# S10B-M-V2_0.net
KiCad netlist of a schematic drawn in Altium Designer
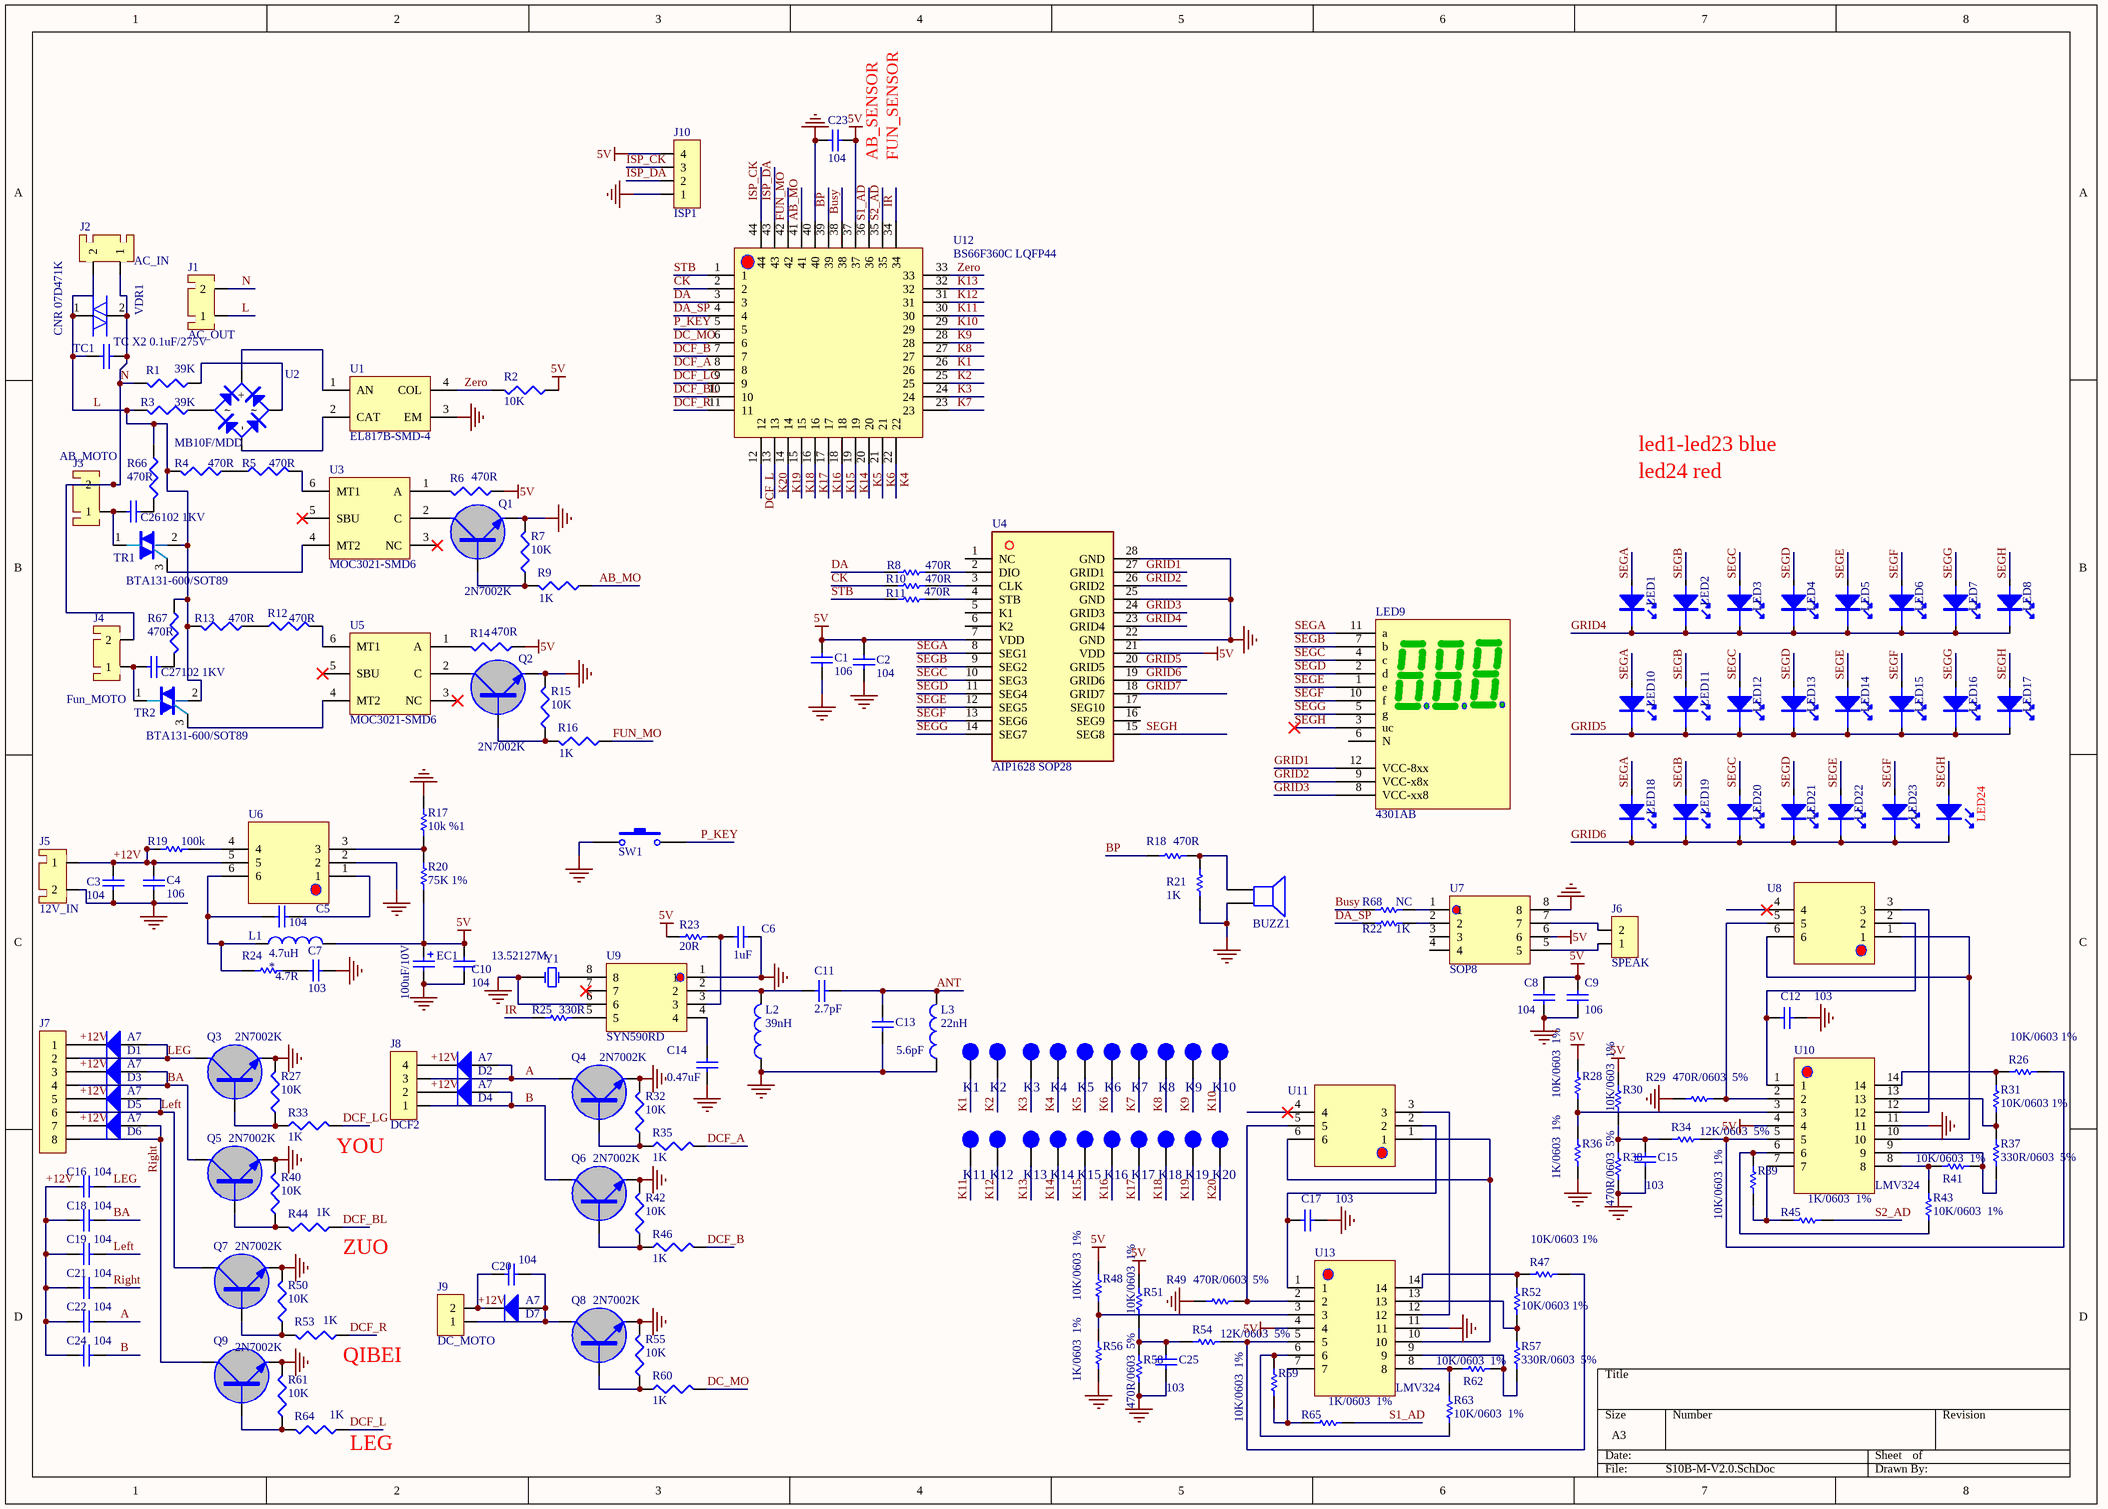
[diagram p0: S10B-M-V2.0.SchDoc]

(export (version "E")
  (design (tool "Eeschema 10.0.6"))
  (components
    (comp (ref "BUZZ1")
      (value "Speaker")
      (footprint "BUZ-1407-7.5")
      (description "Loudspeaker")
      (fields (field (name "MANUFACTURER") "Generic Components"))
      (libsource (lib "Miscellaneous Devices") (part "Speaker"))
    )
    (comp (ref "C1")
      (value "106")
      (footprint "0805C")
      (description "Capacitor")
      (fields
        (field (name "MANUFACTURER") "Generic Components")
        (field (name "PUBLISHER") "Altium Hobart Technology Centre")
      )
      (libsource (lib "Miscellaneous Devices") (part "Cap"))
    )
    (comp (ref "C2")
      (value "104")
      (footprint "0603C")
      (description "Capacitor")
      (fields
        (field (name "MANUFACTURER") "Generic Components")
        (field (name "PUBLISHER") "Altium Hobart Technology Centre")
      )
      (libsource (lib "Miscellaneous Devices") (part "Cap"))
    )
    (comp (ref "C3")
      (value "104")
      (footprint "0603C")
      (description "Capacitor")
      (fields (field (name "PUBLISHER") "Altium Limited"))
      (libsource (lib "Phil") (part "Cap"))
    )
    (comp (ref "C4")
      (value "106")
      (footprint "0805C")
      (description "Capacitor")
      (fields
        (field (name "MANUFACTURER") "Generic Components")
        (field (name "PUBLISHER") "Altium Hobart Technology Centre")
      )
      (libsource (lib "Miscellaneous Devices") (part "Cap"))
    )
    (comp (ref "C5")
      (value "104")
      (footprint "0603C")
      (description "Capacitor")
      (fields
        (field (name "MANUFACTURER") "Generic Components")
        (field (name "PUBLISHER") "Altium Hobart Technology Centre")
      )
      (libsource (lib "Miscellaneous Devices") (part "Cap"))
    )
    (comp (ref "C6")
      (value "1uF")
      (footprint "0603C")
      (description "Capacitor")
      (fields (field (name "PUBLISHER") "Altium Limited"))
      (libsource (lib "Phil") (part "Cap"))
    )
    (comp (ref "C7")
      (value "103")
      (footprint "0603C")
      (description "Capacitor")
      (fields (field (name "PUBLISHER") "Altium Limited"))
      (libsource (lib "Phil") (part "Cap"))
    )
    (comp (ref "C8")
      (value "104")
      (footprint "0603C")
      (description "Capacitor")
      (fields
        (field (name "MANUFACTURER") "Generic Components")
        (field (name "PUBLISHER") "Altium Hobart Technology Centre")
      )
      (libsource (lib "Miscellaneous Devices") (part "Cap"))
    )
    (comp (ref "C9")
      (value "106")
      (footprint "0805C")
      (description "Capacitor")
      (fields
        (field (name "MANUFACTURER") "Generic Components")
        (field (name "PUBLISHER") "Altium Hobart Technology Centre")
      )
      (libsource (lib "Miscellaneous Devices") (part "Cap"))
    )
    (comp (ref "C10")
      (value "104")
      (footprint "0603C")
      (description "Capacitor")
      (fields
        (field (name "MANUFACTURER") "Generic Components")
        (field (name "PUBLISHER") "Altium Hobart Technology Centre")
      )
      (libsource (lib "Miscellaneous Devices") (part "Cap"))
    )
    (comp (ref "C11")
      (value "2.7pF")
      (footprint "0603C")
      (description "Capacitor")
      (fields (field (name "PUBLISHER") "Altium Limited"))
      (libsource (lib "Phil") (part "Cap"))
    )
    (comp (ref "C12")
      (value "103")
      (footprint "0603C")
      (description "Capacitor")
      (fields (field (name "PUBLISHER") "Altium Limited"))
      (libsource (lib "Phil") (part "Cap"))
    )
    (comp (ref "C13")
      (value "5.6pF")
      (footprint "0603C")
      (description "Capacitor")
      (fields (field (name "PUBLISHER") "Altium Limited"))
      (libsource (lib "Phil") (part "Cap"))
    )
    (comp (ref "C14")
      (value "0.47uF")
      (footprint "0603C")
      (description "Capacitor")
      (fields (field (name "PUBLISHER") "Altium Limited"))
      (libsource (lib "Phil") (part "Cap"))
    )
    (comp (ref "C15")
      (value "103")
      (footprint "0603C")
      (description "Capacitor")
      (fields (field (name "PUBLISHER") "Altium Limited"))
      (libsource (lib "Phil") (part "Cap"))
    )
    (comp (ref "C16")
      (value "104")
      (footprint "0603C")
      (description "Capacitor")
      (fields (field (name "PUBLISHER") "Altium Limited"))
      (libsource (lib "Phil") (part "Cap"))
    )
    (comp (ref "C17")
      (value "103")
      (footprint "0603C")
      (description "Capacitor")
      (fields (field (name "PUBLISHER") "Altium Limited"))
      (libsource (lib "Phil") (part "Cap"))
    )
    (comp (ref "C18")
      (value "104")
      (footprint "0603C")
      (description "Capacitor")
      (fields (field (name "PUBLISHER") "Altium Limited"))
      (libsource (lib "Phil") (part "Cap"))
    )
    (comp (ref "C19")
      (value "104")
      (footprint "0603C")
      (description "Capacitor")
      (fields (field (name "PUBLISHER") "Altium Limited"))
      (libsource (lib "Phil") (part "Cap"))
    )
    (comp (ref "C20")
      (value "104")
      (footprint "0603C")
      (description "Capacitor")
      (fields
        (field (name "MANUFACTURER") "Generic Components")
        (field (name "PUBLISHER") "Altium Hobart Technology Centre")
      )
      (libsource (lib "Miscellaneous Devices") (part "Cap"))
    )
    (comp (ref "C21")
      (value "104")
      (footprint "0603C")
      (description "Capacitor")
      (fields (field (name "PUBLISHER") "Altium Limited"))
      (libsource (lib "Phil") (part "Cap"))
    )
    (comp (ref "C22")
      (value "104")
      (footprint "0603C")
      (description "Capacitor")
      (fields (field (name "PUBLISHER") "Altium Limited"))
      (libsource (lib "Phil") (part "Cap"))
    )
    (comp (ref "C23")
      (value "104")
      (footprint "0603C")
      (description "Capacitor")
      (fields (field (name "PUBLISHER") "Altium Limited"))
      (libsource (lib "HF-FOUR-M-1.0") (part "Cap"))
    )
    (comp (ref "C24")
      (value "104")
      (footprint "0603C")
      (description "Capacitor")
      (fields (field (name "PUBLISHER") "Altium Limited"))
      (libsource (lib "Phil") (part "Cap"))
    )
    (comp (ref "C25")
      (value "103")
      (footprint "0603C")
      (description "Capacitor")
      (fields (field (name "PUBLISHER") "Altium Limited"))
      (libsource (lib "Phil") (part "Cap"))
    )
    (comp (ref "C26")
      (value "102 1KV")
      (footprint "1206C")
      (description "Capacitor")
      (fields
        (field (name "MANUFACTURER") "Generic Components")
        (field (name "PUBLISHER") "Altium Hobart Technology Centre")
      )
      (libsource (lib "Miscellaneous Devices") (part "Cap"))
    )
    (comp (ref "C27")
      (value "102 1KV")
      (footprint "1206C")
      (description "Capacitor")
      (fields
        (field (name "MANUFACTURER") "Generic Components")
        (field (name "PUBLISHER") "Altium Hobart Technology Centre")
      )
      (libsource (lib "Miscellaneous Devices") (part "Cap"))
    )
    (comp (ref "D1")
      (value "A7")
      (footprint "SOD-123FL_L2.8-W1.8-LS3.7")
      (description "1 Amp General Purpose Rectifier")
      (fields (field (name "PUBLISHER") "Altium Limited"))
      (libsource (lib "Phil") (part "Diode 1N4007"))
    )
    (comp (ref "D2")
      (value "A7")
      (footprint "SOD-123FL_L2.8-W1.8-LS3.7")
      (description "1 Amp General Purpose Rectifier")
      (fields (field (name "PUBLISHER") "Altium Limited"))
      (libsource (lib "Phil") (part "Diode 1N4007"))
    )
    (comp (ref "D3")
      (value "A7")
      (footprint "SOD-123FL_L2.8-W1.8-LS3.7")
      (description "1 Amp General Purpose Rectifier")
      (fields (field (name "PUBLISHER") "Altium Limited"))
      (libsource (lib "Phil") (part "Diode 1N4007"))
    )
    (comp (ref "D4")
      (value "A7")
      (footprint "SOD-123FL_L2.8-W1.8-LS3.7")
      (description "1 Amp General Purpose Rectifier")
      (fields (field (name "PUBLISHER") "Altium Limited"))
      (libsource (lib "Phil") (part "Diode 1N4007"))
    )
    (comp (ref "D5")
      (value "A7")
      (footprint "SOD-123FL_L2.8-W1.8-LS3.7")
      (description "1 Amp General Purpose Rectifier")
      (fields (field (name "PUBLISHER") "Altium Limited"))
      (libsource (lib "Phil") (part "Diode 1N4007"))
    )
    (comp (ref "D6")
      (value "A7")
      (footprint "SOD-123FL_L2.8-W1.8-LS3.7")
      (description "1 Amp General Purpose Rectifier")
      (fields (field (name "PUBLISHER") "Altium Limited"))
      (libsource (lib "Phil") (part "Diode 1N4007"))
    )
    (comp (ref "D7")
      (value "A7")
      (footprint "SOD-123FL_L2.8-W1.8-LS3.7")
      (description "1 Amp General Purpose Rectifier")
      (fields (field (name "PUBLISHER") "Altium Limited"))
      (libsource (lib "Phil") (part "Diode 1N4007"))
    )
    (comp (ref "EC1")
      (value "100uF/10V")
      (footprint "CAP SMD 6.3*5.5mm")
      (description "Polarized Capacitor (Radial)")
      (fields
        (field (name "MANUFACTURER") "Generic Components")
        (field (name "PUBLISHER") "Altium Hobart Technology Centre")
      )
      (libsource (lib "Miscellaneous Devices") (part "Cap Pol1"))
    )
    (comp (ref "J1")
      (value "AC_OUT")
      (footprint "K-VH3.96-3P")
      (libsource (lib "") (part "PITCH3.96-5.0-2A_1"))
    )
    (comp (ref "J2")
      (value "AC_IN")
      (footprint "K-VH3.96-3P")
      (libsource (lib "SCH Connector(2019-4-13)") (part "PITCH3.96-5.0-2A"))
    )
    (comp (ref "J3")
      (value "AB_MOTO")
      (footprint "K-VH3.96-3P")
      (libsource (lib "") (part "PITCH3.96-5.0-2A_1"))
    )
    (comp (ref "J4")
      (value "Fun_MOTO")
      (footprint "K-VH3.96-3P")
      (libsource (lib "") (part "PITCH3.96-5.0-2A_1"))
    )
    (comp (ref "J5")
      (value "12V_IN")
      (footprint "CON2-SMD-XHB 2*2.5MM")
      (libsource (lib "SCH Connector(2019-4-13)") (part "PITCH2.5-2A"))
    )
    (comp (ref "J6")
      (value "SPEAK")
      (footprint "CON2-SMD_PH2.0-1X2PW")
      (libsource (lib "Phil") (part "CON2"))
    )
    (comp (ref "J7")
      (value "~")
      (footprint "CON8-SMD-XHB 8*2.5MM")
      (libsource (lib "HF-FOUR-M-1.0") (part "CON8"))
    )
    (comp (ref "J8")
      (value "DCF2")
      (footprint "CON4-SMD_4P-P2.54_XH2.54-4AB")
      (libsource (lib "") (part "CON4_1"))
    )
    (comp (ref "J9")
      (value "DC_MOTO")
      (footprint "CON2-SMD-XHB 2*2.5MM")
      (libsource (lib "") (part "CON2_1"))
    )
    (comp (ref "J10") (value "ISP1") (footprint "CON4 -2.54-H") (libsource (lib "Phil") (part "CON4")))
    (comp (ref "K1")
      (value "Φ15 H8mm弹簧")
      (footprint "TK_HF-13*13*8")
      (libsource (lib "HF-FOUR-M-1.0") (part "TOUCH-PAD"))
    )
    (comp (ref "K2")
      (value "Φ15 H8mm弹簧")
      (footprint "TK_HF-13*13*8")
      (libsource (lib "HF-FOUR-M-1.0") (part "TOUCH-PAD"))
    )
    (comp (ref "K3")
      (value "Φ15 H8mm弹簧")
      (footprint "TK_HF-13*13*8")
      (libsource (lib "HF-FOUR-M-1.0") (part "TOUCH-PAD"))
    )
    (comp (ref "K4")
      (value "Φ15 H8mm弹簧")
      (footprint "TK_HF-13*13*8")
      (libsource (lib "HF-FOUR-M-1.0") (part "TOUCH-PAD"))
    )
    (comp (ref "K5")
      (value "Φ15 H8mm弹簧")
      (footprint "TK_HF-13*13*8")
      (libsource (lib "HF-FOUR-M-1.0") (part "TOUCH-PAD"))
    )
    (comp (ref "K6")
      (value "Φ15 H8mm弹簧")
      (footprint "TK_HF-13*13*8")
      (libsource (lib "HF-FOUR-M-1.0") (part "TOUCH-PAD"))
    )
    (comp (ref "K7")
      (value "Φ15 H8mm弹簧")
      (footprint "TK_HF-13*13*8")
      (libsource (lib "HF-FOUR-M-1.0") (part "TOUCH-PAD"))
    )
    (comp (ref "K8")
      (value "Φ15 H8mm弹簧")
      (footprint "TK_HF-13*13*8")
      (libsource (lib "HF-FOUR-M-1.0") (part "TOUCH-PAD"))
    )
    (comp (ref "K9")
      (value "Φ15 H8mm弹簧")
      (footprint "TK_HF-13*13*8")
      (libsource (lib "HF-FOUR-M-1.0") (part "TOUCH-PAD"))
    )
    (comp (ref "K10")
      (value "Φ15 H8mm弹簧")
      (footprint "TK_HF-13*13*8")
      (libsource (lib "HF-FOUR-M-1.0") (part "TOUCH-PAD"))
    )
    (comp (ref "K11")
      (value "Φ15 H8mm弹簧")
      (footprint "TK_HF-13*13*8")
      (libsource (lib "HF-FOUR-M-1.0") (part "TOUCH-PAD"))
    )
    (comp (ref "K12")
      (value "Φ15 H8mm弹簧")
      (footprint "TK_HF-13*13*8")
      (libsource (lib "HF-FOUR-M-1.0") (part "TOUCH-PAD"))
    )
    (comp (ref "K13")
      (value "Φ15 H8mm弹簧")
      (footprint "TK_HF-13*13*8")
      (libsource (lib "HF-FOUR-M-1.0") (part "TOUCH-PAD"))
    )
    (comp (ref "K14")
      (value "Φ15 H8mm弹簧")
      (footprint "TK_HF-13*13*8")
      (libsource (lib "HF-FOUR-M-1.0") (part "TOUCH-PAD"))
    )
    (comp (ref "K15")
      (value "Φ15 H8mm弹簧")
      (footprint "TK_HF-13*13*8")
      (libsource (lib "HF-FOUR-M-1.0") (part "TOUCH-PAD"))
    )
    (comp (ref "K16")
      (value "Φ15 H8mm弹簧")
      (footprint "TK_HF-13*13*8")
      (libsource (lib "HF-FOUR-M-1.0") (part "TOUCH-PAD"))
    )
    (comp (ref "K17")
      (value "Φ15 H8mm弹簧")
      (footprint "TK_HF-13*13*8")
      (libsource (lib "HF-FOUR-M-1.0") (part "TOUCH-PAD"))
    )
    (comp (ref "K18")
      (value "Φ15 H8mm弹簧")
      (footprint "TK_HF-13*13*8")
      (libsource (lib "HF-FOUR-M-1.0") (part "TOUCH-PAD"))
    )
    (comp (ref "K19")
      (value "Φ15 H8mm弹簧")
      (footprint "TK_HF-13*13*8")
      (libsource (lib "HF-FOUR-M-1.0") (part "TOUCH-PAD"))
    )
    (comp (ref "K20")
      (value "Φ15 H8mm弹簧")
      (footprint "TK_HF-13*13*8")
      (libsource (lib "HF-FOUR-M-1.0") (part "TOUCH-PAD"))
    )
    (comp (ref "L1")
      (value "4.7uH")
      (footprint "INDC5050")
      (description "Inductor")
      (fields (field (name "ALTIUM_VALUE") "*") (field (name "PUBLISHER") "Altium Limited"))
      (libsource (lib "Phil") (part "Inductor"))
    )
    (comp (ref "L2")
      (value "39nH")
      (footprint "0603R")
      (description "Inductor")
      (fields (field (name "PUBLISHER") "Altium Limited"))
      (libsource (lib "Phil") (part "Inductor"))
    )
    (comp (ref "L3")
      (value "22nH")
      (footprint "0603R")
      (description "Inductor")
      (fields (field (name "PUBLISHER") "Altium Limited"))
      (libsource (lib "Phil") (part "Inductor"))
    )
    (comp (ref "LED1") (value "LED_0603") (footprint "LED_0603") (libsource (lib "Phil") (part "LED")))
    (comp (ref "LED2") (value "LED_0603") (footprint "LED_0603") (libsource (lib "Phil") (part "LED")))
    (comp (ref "LED3") (value "LED_0603") (footprint "LED_0603") (libsource (lib "Phil") (part "LED")))
    (comp (ref "LED4") (value "LED_0603") (footprint "LED_0603") (libsource (lib "Phil") (part "LED")))
    (comp (ref "LED5") (value "LED_0603") (footprint "LED_0603") (libsource (lib "Phil") (part "LED")))
    (comp (ref "LED6") (value "LED_0603") (footprint "LED_0603") (libsource (lib "Phil") (part "LED")))
    (comp (ref "LED7") (value "LED_0603") (footprint "LED_0603") (libsource (lib "Phil") (part "LED")))
    (comp (ref "LED8") (value "LED_0603") (footprint "LED_0603") (libsource (lib "Phil") (part "LED")))
    (comp (ref "LED9")
      (value "4301AB")
      (footprint "LED4031-SEG-TH_12P-L30.1-W16.0-P2.54-S12.70-BL")
      (libsource (lib "SCH LED-LCD(2019-3-7)") (part "LED-888-COM VCC-1"))
    )
    (comp (ref "LED10") (value "LED_0603") (footprint "LED_0603") (libsource (lib "Phil") (part "LED")))
    (comp (ref "LED11") (value "LED_0603") (footprint "LED_0603") (libsource (lib "Phil") (part "LED")))
    (comp (ref "LED12") (value "LED_0603") (footprint "LED_0603") (libsource (lib "Phil") (part "LED")))
    (comp (ref "LED13") (value "LED_0603") (footprint "LED_0603") (libsource (lib "Phil") (part "LED")))
    (comp (ref "LED14") (value "LED_0603") (footprint "LED_0603") (libsource (lib "Phil") (part "LED")))
    (comp (ref "LED15") (value "LED_0603") (footprint "LED_0603") (libsource (lib "Phil") (part "LED")))
    (comp (ref "LED16") (value "LED_0603") (footprint "LED_0603") (libsource (lib "Phil") (part "LED")))
    (comp (ref "LED17") (value "LED_0603") (footprint "LED_0603") (libsource (lib "Phil") (part "LED")))
    (comp (ref "LED18") (value "LED_0603") (footprint "LED_0603") (libsource (lib "Phil") (part "LED")))
    (comp (ref "LED19") (value "LED_0603") (footprint "LED_0603") (libsource (lib "Phil") (part "LED")))
    (comp (ref "LED20") (value "LED_0603") (footprint "LED_0603") (libsource (lib "Phil") (part "LED")))
    (comp (ref "LED21") (value "LED_0603") (footprint "LED_0603") (libsource (lib "Phil") (part "LED")))
    (comp (ref "LED22") (value "LED_0603") (footprint "LED_0603") (libsource (lib "Phil") (part "LED")))
    (comp (ref "LED23") (value "LED_0603") (footprint "LED_0603") (libsource (lib "Phil") (part "LED")))
    (comp (ref "LED24") (value "LED_0603") (footprint "LED_0603") (libsource (lib "Phil") (part "LED")))
    (comp (ref "Q1")
      (value "2N7002K")
      (footprint "SOT-23 - MOS")
      (libsource (lib "SCH-Transistor-Triac-Mosfet(2018-9-19-1)") (part "NPN-8050-BCE-25V/500mA"))
    )
    (comp (ref "Q2")
      (value "2N7002K")
      (footprint "SOT-23 - MOS")
      (libsource (lib "SCH-Transistor-Triac-Mosfet(2018-9-19-1)") (part "NPN-8050-BCE-25V/500mA"))
    )
    (comp (ref "Q3")
      (value "2N7002K")
      (footprint "SOT-23 - MOS")
      (libsource (lib "SCH-Transistor-Triac-Mosfet(2018-9-19-1)") (part "NPN-8050-BCE-25V/500mA"))
    )
    (comp (ref "Q4")
      (value "2N7002K")
      (footprint "SOT-23 - MOS")
      (libsource (lib "SCH-Transistor-Triac-Mosfet(2018-9-19-1)") (part "NPN-8050-BCE-25V/500mA"))
    )
    (comp (ref "Q5")
      (value "2N7002K")
      (footprint "SOT-23 - MOS")
      (libsource (lib "SCH-Transistor-Triac-Mosfet(2018-9-19-1)") (part "NPN-8050-BCE-25V/500mA"))
    )
    (comp (ref "Q6")
      (value "2N7002K")
      (footprint "SOT-23 - MOS")
      (libsource (lib "SCH-Transistor-Triac-Mosfet(2018-9-19-1)") (part "NPN-8050-BCE-25V/500mA"))
    )
    (comp (ref "Q7")
      (value "2N7002K")
      (footprint "SOT-23 - MOS")
      (libsource (lib "SCH-Transistor-Triac-Mosfet(2018-9-19-1)") (part "NPN-8050-BCE-25V/500mA"))
    )
    (comp (ref "Q8")
      (value "2N7002K")
      (footprint "SOT-23 - MOS")
      (libsource (lib "SCH-Transistor-Triac-Mosfet(2018-9-19-1)") (part "NPN-8050-BCE-25V/500mA"))
    )
    (comp (ref "Q9")
      (value "2N7002K")
      (footprint "SOT-23 - MOS")
      (libsource (lib "SCH-Transistor-Triac-Mosfet(2018-9-19-1)") (part "NPN-8050-BCE-25V/500mA"))
    )
    (comp (ref "R1")
      (value "39K")
      (footprint "1206R")
      (libsource (lib "SCH Resistor(2019-6-10)") (part "1Ω±1%/0805-1206"))
    )
    (comp (ref "R2")
      (value "10K")
      (footprint "0603")
      (libsource (lib "SCH Resistor(2019-6-10)") (part "1Ω±1%/0603-0805"))
    )
    (comp (ref "R3")
      (value "39K")
      (footprint "1206R")
      (libsource (lib "SCH Resistor(2019-6-10)") (part "1Ω±1%/0805-1206"))
    )
    (comp (ref "R4")
      (value "470R")
      (footprint "1206R")
      (libsource (lib "SCH Resistor(2019-6-10)") (part "1Ω±1%/0805-1206"))
    )
    (comp (ref "R5")
      (value "470R")
      (footprint "1206R")
      (libsource (lib "SCH Resistor(2019-6-10)") (part "1Ω±1%/0805-1206"))
    )
    (comp (ref "R6")
      (value "470R")
      (footprint "0603")
      (libsource (lib "SCH Resistor(2019-6-10)") (part "1Ω±1%/0603-0805"))
    )
    (comp (ref "R7")
      (value "10K")
      (footprint "0603")
      (libsource (lib "SCH Resistor(2019-6-10)") (part "1Ω±1%/0603-0805"))
    )
    (comp (ref "R8")
      (value "470R")
      (footprint "0603R")
      (description "Resistor")
      (fields (field (name "PUBLISHER") "Altium Limited"))
      (libsource (lib "Phil") (part "Res1"))
    )
    (comp (ref "R9")
      (value "1K")
      (footprint "0603")
      (libsource (lib "SCH Resistor(2019-6-10)") (part "1Ω±1%/0603-0805"))
    )
    (comp (ref "R10")
      (value "470R")
      (footprint "0603R")
      (description "Resistor")
      (fields (field (name "PUBLISHER") "Altium Limited"))
      (libsource (lib "Phil") (part "Res1"))
    )
    (comp (ref "R11")
      (value "470R")
      (footprint "0603R")
      (description "Resistor")
      (fields (field (name "PUBLISHER") "Altium Limited"))
      (libsource (lib "Phil") (part "Res1"))
    )
    (comp (ref "R12")
      (value "470R")
      (footprint "1206R")
      (libsource (lib "SCH Resistor(2019-6-10)") (part "1Ω±1%/0805-1206"))
    )
    (comp (ref "R13")
      (value "470R")
      (footprint "1206R")
      (libsource (lib "SCH Resistor(2019-6-10)") (part "1Ω±1%/0805-1206"))
    )
    (comp (ref "R14")
      (value "470R")
      (footprint "0603")
      (libsource (lib "SCH Resistor(2019-6-10)") (part "1Ω±1%/0603-0805"))
    )
    (comp (ref "R15")
      (value "10K")
      (footprint "0603")
      (libsource (lib "SCH Resistor(2019-6-10)") (part "1Ω±1%/0603-0805"))
    )
    (comp (ref "R16")
      (value "1K")
      (footprint "0603")
      (libsource (lib "SCH Resistor(2019-6-10)") (part "1Ω±1%/0603-0805"))
    )
    (comp (ref "R17")
      (value "10k %1")
      (footprint "0603R")
      (description "Resistor")
      (fields (field (name "PUBLISHER") "Altium Limited"))
      (libsource (lib "Phil") (part "Res1"))
    )
    (comp (ref "R18")
      (value "470R")
      (footprint "0603R")
      (description "Resistor")
      (fields (field (name "PUBLISHER") "Altium Limited"))
      (libsource (lib "Phil") (part "Res1"))
    )
    (comp (ref "R19")
      (value "100k")
      (footprint "0603R")
      (description "Resistor")
      (fields (field (name "PUBLISHER") "Altium Limited"))
      (libsource (lib "Phil") (part "Res1"))
    )
    (comp (ref "R20")
      (value "75K 1%")
      (footprint "0603R")
      (description "Resistor")
      (fields (field (name "PUBLISHER") "Altium Limited"))
      (libsource (lib "Phil") (part "Res1"))
    )
    (comp (ref "R21")
      (value "1K")
      (footprint "0603R")
      (description "Resistor")
      (fields (field (name "PUBLISHER") "Altium Limited"))
      (libsource (lib "Phil") (part "Res1"))
    )
    (comp (ref "R22")
      (value "1K")
      (footprint "0603R")
      (description "Resistor")
      (fields (field (name "PUBLISHER") "Altium Limited"))
      (libsource (lib "Phil") (part "Res1"))
    )
    (comp (ref "R23")
      (value "20R")
      (footprint "0603R")
      (description "Resistor")
      (fields (field (name "PUBLISHER") "Altium Limited"))
      (libsource (lib "Phil") (part "Res1"))
    )
    (comp (ref "R24")
      (value "4.7R")
      (footprint "0603R")
      (description "Resistor")
      (fields (field (name "PUBLISHER") "Altium Limited"))
      (libsource (lib "Phil") (part "Res1"))
    )
    (comp (ref "R25")
      (value "330R")
      (footprint "0603R")
      (description "Resistor")
      (fields (field (name "PUBLISHER") "Altium Limited"))
      (libsource (lib "Phil") (part "Res1"))
    )
    (comp (ref "R26")
      (value "10K/0603 1%")
      (footprint "0603R")
      (description "Resistor")
      (fields (field (name "PUBLISHER") "Altium Limited"))
      (libsource (lib "Phil") (part "Res1"))
    )
    (comp (ref "R27")
      (value "10K")
      (footprint "0603")
      (libsource (lib "SCH Resistor(2019-6-10)") (part "1Ω±1%/0603-0805"))
    )
    (comp (ref "R28")
      (value "10K/0603  1%")
      (footprint "0603R")
      (description "Resistor")
      (fields (field (name "PUBLISHER") "Altium Limited"))
      (libsource (lib "Phil") (part "Res1"))
    )
    (comp (ref "R29")
      (value "470R/0603  5%")
      (footprint "0603R")
      (description "Resistor")
      (fields (field (name "PUBLISHER") "Altium Limited"))
      (libsource (lib "Phil") (part "Res1"))
    )
    (comp (ref "R30")
      (value "10K/0603  1%")
      (footprint "0603R")
      (description "Resistor")
      (fields (field (name "PUBLISHER") "Altium Limited"))
      (libsource (lib "Phil") (part "Res1"))
    )
    (comp (ref "R31")
      (value "10K/0603 1%")
      (footprint "0603R")
      (description "Resistor")
      (fields (field (name "PUBLISHER") "Altium Limited"))
      (libsource (lib "Phil") (part "Res1"))
    )
    (comp (ref "R32")
      (value "10K")
      (footprint "0603")
      (libsource (lib "SCH Resistor(2019-6-10)") (part "1Ω±1%/0603-0805"))
    )
    (comp (ref "R33")
      (value "1K")
      (footprint "0603")
      (libsource (lib "SCH Resistor(2019-6-10)") (part "1Ω±1%/0603-0805"))
    )
    (comp (ref "R34")
      (value "12K/0603  5%")
      (footprint "0603R")
      (description "Resistor")
      (fields (field (name "PUBLISHER") "Altium Limited"))
      (libsource (lib "Phil") (part "Res1"))
    )
    (comp (ref "R35")
      (value "1K")
      (footprint "0603")
      (libsource (lib "SCH Resistor(2019-6-10)") (part "1Ω±1%/0603-0805"))
    )
    (comp (ref "R36")
      (value "1K/0603  1%")
      (footprint "0603R")
      (description "Resistor")
      (fields (field (name "PUBLISHER") "Altium Limited"))
      (libsource (lib "Phil") (part "Res1"))
    )
    (comp (ref "R37")
      (value "330R/0603  5%")
      (footprint "0603R")
      (description "Resistor")
      (fields (field (name "PUBLISHER") "Altium Limited"))
      (libsource (lib "Phil") (part "Res1"))
    )
    (comp (ref "R38")
      (value "470R/0603  5%")
      (footprint "0603R")
      (description "Resistor")
      (fields (field (name "PUBLISHER") "Altium Limited"))
      (libsource (lib "Phil") (part "Res1"))
    )
    (comp (ref "R39")
      (value "10K/0603  1%")
      (footprint "0603R")
      (description "Resistor")
      (fields (field (name "PUBLISHER") "Altium Limited"))
      (libsource (lib "Phil") (part "Res1"))
    )
    (comp (ref "R40")
      (value "10K")
      (footprint "0603")
      (libsource (lib "SCH Resistor(2019-6-10)") (part "1Ω±1%/0603-0805"))
    )
    (comp (ref "R41")
      (value "10K/0603  1%")
      (footprint "0603R")
      (description "Resistor")
      (fields (field (name "PUBLISHER") "Altium Limited"))
      (libsource (lib "Phil") (part "Res1"))
    )
    (comp (ref "R42")
      (value "10K")
      (footprint "0603")
      (libsource (lib "SCH Resistor(2019-6-10)") (part "1Ω±1%/0603-0805"))
    )
    (comp (ref "R43")
      (value "10K/0603  1%")
      (footprint "0603R")
      (description "Resistor")
      (fields (field (name "PUBLISHER") "Altium Limited"))
      (libsource (lib "Phil") (part "Res1"))
    )
    (comp (ref "R44")
      (value "1K")
      (footprint "0603")
      (libsource (lib "SCH Resistor(2019-6-10)") (part "1Ω±1%/0603-0805"))
    )
    (comp (ref "R45")
      (value "1K/0603  1%")
      (footprint "0603R")
      (description "Resistor")
      (fields (field (name "PUBLISHER") "Altium Limited"))
      (libsource (lib "Phil") (part "Res1"))
    )
    (comp (ref "R46")
      (value "1K")
      (footprint "0603")
      (libsource (lib "SCH Resistor(2019-6-10)") (part "1Ω±1%/0603-0805"))
    )
    (comp (ref "R47")
      (value "10K/0603 1%")
      (footprint "0603R")
      (description "Resistor")
      (fields (field (name "PUBLISHER") "Altium Limited"))
      (libsource (lib "Phil") (part "Res1"))
    )
    (comp (ref "R48")
      (value "10K/0603  1%")
      (footprint "0603R")
      (description "Resistor")
      (fields (field (name "PUBLISHER") "Altium Limited"))
      (libsource (lib "Phil") (part "Res1"))
    )
    (comp (ref "R49")
      (value "470R/0603  5%")
      (footprint "0603R")
      (description "Resistor")
      (fields (field (name "PUBLISHER") "Altium Limited"))
      (libsource (lib "Phil") (part "Res1"))
    )
    (comp (ref "R50")
      (value "10K")
      (footprint "0603")
      (libsource (lib "SCH Resistor(2019-6-10)") (part "1Ω±1%/0603-0805"))
    )
    (comp (ref "R51")
      (value "10K/0603  1%")
      (footprint "0603R")
      (description "Resistor")
      (fields (field (name "PUBLISHER") "Altium Limited"))
      (libsource (lib "Phil") (part "Res1"))
    )
    (comp (ref "R52")
      (value "10K/0603 1%")
      (footprint "0603R")
      (description "Resistor")
      (fields (field (name "PUBLISHER") "Altium Limited"))
      (libsource (lib "Phil") (part "Res1"))
    )
    (comp (ref "R53")
      (value "1K")
      (footprint "0603")
      (libsource (lib "SCH Resistor(2019-6-10)") (part "1Ω±1%/0603-0805"))
    )
    (comp (ref "R54")
      (value "12K/0603  5%")
      (footprint "0603R")
      (description "Resistor")
      (fields (field (name "PUBLISHER") "Altium Limited"))
      (libsource (lib "Phil") (part "Res1"))
    )
    (comp (ref "R55")
      (value "10K")
      (footprint "0603")
      (libsource (lib "SCH Resistor(2019-6-10)") (part "1Ω±1%/0603-0805"))
    )
    (comp (ref "R56")
      (value "1K/0603  1%")
      (footprint "0603R")
      (description "Resistor")
      (fields (field (name "PUBLISHER") "Altium Limited"))
      (libsource (lib "Phil") (part "Res1"))
    )
    (comp (ref "R57")
      (value "330R/0603  5%")
      (footprint "0603R")
      (description "Resistor")
      (fields (field (name "PUBLISHER") "Altium Limited"))
      (libsource (lib "Phil") (part "Res1"))
    )
    (comp (ref "R58")
      (value "470R/0603  5%")
      (footprint "0603R")
      (description "Resistor")
      (fields (field (name "PUBLISHER") "Altium Limited"))
      (libsource (lib "Phil") (part "Res1"))
    )
    (comp (ref "R59")
      (value "10K/0603  1%")
      (footprint "0603R")
      (description "Resistor")
      (fields (field (name "PUBLISHER") "Altium Limited"))
      (libsource (lib "Phil") (part "Res1"))
    )
    (comp (ref "R60")
      (value "1K")
      (footprint "0603")
      (libsource (lib "SCH Resistor(2019-6-10)") (part "1Ω±1%/0603-0805"))
    )
    (comp (ref "R61")
      (value "10K")
      (footprint "0603")
      (libsource (lib "SCH Resistor(2019-6-10)") (part "1Ω±1%/0603-0805"))
    )
    (comp (ref "R62")
      (value "10K/0603  1%")
      (footprint "0603R")
      (description "Resistor")
      (fields (field (name "PUBLISHER") "Altium Limited"))
      (libsource (lib "Phil") (part "Res1"))
    )
    (comp (ref "R63")
      (value "10K/0603  1%")
      (footprint "0603R")
      (description "Resistor")
      (fields (field (name "PUBLISHER") "Altium Limited"))
      (libsource (lib "Phil") (part "Res1"))
    )
    (comp (ref "R64")
      (value "1K")
      (footprint "0603")
      (libsource (lib "SCH Resistor(2019-6-10)") (part "1Ω±1%/0603-0805"))
    )
    (comp (ref "R65")
      (value "1K/0603  1%")
      (footprint "0603R")
      (description "Resistor")
      (fields (field (name "PUBLISHER") "Altium Limited"))
      (libsource (lib "Phil") (part "Res1"))
    )
    (comp (ref "R66")
      (value "470R")
      (footprint "1206R")
      (libsource (lib "SCH Resistor(2019-6-10)") (part "1Ω±1%/0805-1206"))
    )
    (comp (ref "R67")
      (value "470R")
      (footprint "1206R")
      (libsource (lib "SCH Resistor(2019-6-10)") (part "1Ω±1%/0805-1206"))
    )
    (comp (ref "R68")
      (value "NC")
      (footprint "0603R")
      (description "Resistor")
      (fields (field (name "PUBLISHER") "Altium Limited"))
      (libsource (lib "Phil") (part "Res1"))
    )
    (comp (ref "SW1")
      (value "SW-PB")
      (footprint "BUTTON-SMD-6*6*10")
      (description "Switch")
      (fields (field (name "PUBLISHER") "Altium Limited"))
      (libsource (lib "Phil") (part "SW-PB"))
    )
    (comp (ref "TC1")
      (value "TC X2 0.1uF/275V")
      (footprint "CAP-TH_L13.0-W6.0-P10.00-D0.6")
      (libsource (lib "TEL SCH") (part "CAP1"))
    )
    (comp (ref "TR1")
      (value "BTA131-600/SOT89")
      (footprint "SOT-89 BT131-600")
      (libsource (lib "TEL SCH") (part "Triac"))
    )
    (comp (ref "TR2")
      (value "BTA131-600/SOT89")
      (footprint "SOT-89 BT131-600")
      (libsource (lib "TEL SCH") (part "Triac"))
    )
    (comp (ref "U1")
      (value "EL817B-SMD-4")
      (footprint "PC817-smd")
      (libsource (lib "SCH IC-Power(2019-2-14)") (part "EL817-DIP-4"))
    )
    (comp (ref "U2")
      (value "MB10F/MDD")
      (footprint "DB-MB10F")
      (description "Diode Bridge")
      (libsource (lib "SCH Diode-Bridge-Zener(2018-10-15)") (part "BD-ABS10/MB10S"))
    )
    (comp (ref "U3")
      (value "MOC3021-SMD6")
      (footprint "SMD6")
      (libsource (lib "SCH IC-Power(2019-2-14)") (part "MOC3021-DIP-6"))
    )
    (comp (ref "U4")
      (value "AIP1628 SOP28")
      (footprint "SOP28(300MIL)")
      (description "LED driver, SOP28")
      (fields (field (name "MANUFACTURER") "Generic Components"))
      (libsource (lib "Phil") (part "TM1628 SOP28"))
    )
    (comp (ref "U5")
      (value "MOC3021-SMD6")
      (footprint "SMD6")
      (libsource (lib "SCH IC-Power(2019-2-14)") (part "MOC3021-DIP-6"))
    )
    (comp (ref "U6") (value "HT7712") (footprint "SOT23-6_M") (libsource (lib "Phil") (part "SOP6")))
    (comp (ref "U7") (value "SOP8") (footprint "SOP8-SS") (libsource (lib "") (part "SOP8_1")))
    (comp (ref "U8") (value "SOP6") (footprint "PSG010R/S") (libsource (lib "Phil") (part "SOP6")))
    (comp (ref "U9") (value "SYN590RD") (footprint "SOP8(5.1*6.2mm)") (libsource (lib "Phil") (part "SOP8")))
    (comp (ref "U10") (value "LMV324") (footprint "SOP14(150mil)") (libsource (lib "Phil") (part "SOP14")))
    (comp (ref "U11") (value "SOP6") (footprint "PSG010R/S") (libsource (lib "Phil") (part "SOP6")))
    (comp (ref "U12")
      (value "BS66F360C LQFP44")
      (footprint "LQFP44")
      (description "BS66F360C")
      (libsource (lib "Phil") (part "LQFP44"))
    )
    (comp (ref "U13") (value "LMV324") (footprint "SOP14(150mil)") (libsource (lib "Phil") (part "SOP14")))
    (comp (ref "VDR1")
      (value "CNR 07D471K")
      (footprint "RES-TH_L9.0-W5.0-P5-D0.7-S3.00")
      (libsource (lib "LZB_SCH") (part "VAR"))
    )
    (comp (ref "Y1")
      (value "13.52127M")
      (footprint "HC-49S_L11.4-W4.8")
      (description "Crystal Oscillator")
      (fields (field (name "PUBLISHER") "Altium Limited"))
      (libsource (lib "Phil") (part "XTAL"))
    )
  )
  (nets
    (net (code "1") (name "/+12V") (class "Default")
      (node (ref "C16") (pin "1") (pinfunction "1_1") (pintype "passive"))
      (node (ref "C18") (pin "1") (pinfunction "1_1") (pintype "passive"))
      (node (ref "C19") (pin "1") (pinfunction "1_1") (pintype "passive"))
      (node (ref "C20") (pin "1") (pinfunction "1_1") (pintype "passive"))
      (node (ref "C21") (pin "1") (pinfunction "1_1") (pintype "passive"))
      (node (ref "C22") (pin "1") (pinfunction "1_1") (pintype "passive"))
      (node (ref "C24") (pin "1") (pinfunction "1_1") (pintype "passive"))
      (node (ref "C3") (pin "1") (pinfunction "1_1") (pintype "passive"))
      (node (ref "C4") (pin "1") (pinfunction "1_1") (pintype "passive"))
      (node (ref "D1") (pin "2") (pinfunction "K_2") (pintype "passive"))
      (node (ref "D2") (pin "2") (pinfunction "K_2") (pintype "passive"))
      (node (ref "D3") (pin "2") (pinfunction "K_2") (pintype "passive"))
      (node (ref "D4") (pin "2") (pinfunction "K_2") (pintype "passive"))
      (node (ref "D5") (pin "2") (pinfunction "K_2") (pintype "passive"))
      (node (ref "D6") (pin "2") (pinfunction "K_2") (pintype "passive"))
      (node (ref "D7") (pin "2") (pinfunction "K_2") (pintype "passive"))
      (node (ref "J5") (pin "1") (pinfunction "1_1") (pintype "passive"))
      (node (ref "J7") (pin "1") (pinfunction "1_1") (pintype "passive"))
      (node (ref "J7") (pin "3") (pinfunction "3_3") (pintype "passive"))
      (node (ref "J7") (pin "5") (pinfunction "5_5") (pintype "passive"))
      (node (ref "J7") (pin "7") (pinfunction "7_7") (pintype "passive"))
      (node (ref "J8") (pin "2") (pinfunction "2_2") (pintype "passive"))
      (node (ref "J8") (pin "4") (pinfunction "4_4") (pintype "passive"))
      (node (ref "J9") (pin "2") (pinfunction "2_2") (pintype "passive"))
      (node (ref "R19") (pin "1") (pinfunction "1_1") (pintype "passive"))
      (node (ref "U6") (pin "5") (pinfunction "5_5") (pintype "passive"))
    )
    (net (code "2") (name "/A") (class "Default")
      (node (ref "C22") (pin "2") (pinfunction "2_2") (pintype "passive"))
      (node (ref "D2") (pin "1") (pinfunction "A_1") (pintype "passive"))
      (node (ref "J8") (pin "3") (pinfunction "3_3") (pintype "passive"))
      (node (ref "Q4") (pin "C") (pinfunction "C_C") (pintype "passive"))
    )
    (net (code "3") (name "/AB_MO") (class "Default")
      (node (ref "R9") (pin "1") (pintype "passive"))
      (node (ref "U12") (pin "41") (pinfunction "41_41") (pintype "passive"))
    )
    (net (code "4") (name "/ANT") (class "Default")
      (node (ref "C11") (pin "1") (pinfunction "1_1") (pintype "passive"))
      (node (ref "C13") (pin "2") (pinfunction "2_2") (pintype "passive"))
      (node (ref "L3") (pin "2") (pinfunction "2_2") (pintype "passive"))
    )
    (net (code "5") (name "/B") (class "Default")
      (node (ref "C24") (pin "2") (pinfunction "2_2") (pintype "passive"))
      (node (ref "D4") (pin "1") (pinfunction "A_1") (pintype "passive"))
      (node (ref "J8") (pin "1") (pinfunction "1_1") (pintype "passive"))
      (node (ref "Q6") (pin "C") (pinfunction "C_C") (pintype "passive"))
    )
    (net (code "6") (name "/BA") (class "Default")
      (node (ref "C18") (pin "2") (pinfunction "2_2") (pintype "passive"))
      (node (ref "D3") (pin "1") (pinfunction "A_1") (pintype "passive"))
      (node (ref "J7") (pin "4") (pinfunction "4_4") (pintype "passive"))
      (node (ref "Q5") (pin "C") (pinfunction "C_C") (pintype "passive"))
    )
    (net (code "7") (name "/BP") (class "Default")
      (node (ref "R18") (pin "2") (pinfunction "2_2") (pintype "passive"))
      (node (ref "U12") (pin "39") (pinfunction "39_39") (pintype "passive"))
    )
    (net (code "8") (name "/Busy") (class "Default")
      (node (ref "R68") (pin "1") (pinfunction "1_1") (pintype "passive"))
      (node (ref "U12") (pin "38") (pinfunction "38_38") (pintype "passive"))
    )
    (net (code "9") (name "/CK") (class "Default")
      (node (ref "R10") (pin "1") (pinfunction "1_1") (pintype "passive"))
      (node (ref "U12") (pin "2") (pinfunction "2_2") (pintype "passive"))
    )
    (net (code "10") (name "/DA") (class "Default")
      (node (ref "R8") (pin "1") (pinfunction "1_1") (pintype "passive"))
      (node (ref "U12") (pin "3") (pinfunction "3_3") (pintype "passive"))
    )
    (net (code "11") (name "/DA_SP") (class "Default")
      (node (ref "R22") (pin "1") (pinfunction "1_1") (pintype "passive"))
      (node (ref "U12") (pin "4") (pinfunction "4_4") (pintype "passive"))
    )
    (net (code "12") (name "/DCF_A") (class "Default")
      (node (ref "R35") (pin "2") (pintype "passive"))
      (node (ref "U12") (pin "8") (pinfunction "8_8") (pintype "passive"))
    )
    (net (code "13") (name "/DCF_B") (class "Default")
      (node (ref "R46") (pin "2") (pintype "passive"))
      (node (ref "U12") (pin "7") (pinfunction "7_7") (pintype "passive"))
    )
    (net (code "14") (name "/DCF_BL") (class "Default")
      (node (ref "R44") (pin "1") (pintype "passive"))
      (node (ref "U12") (pin "10") (pinfunction "10_10") (pintype "passive"))
    )
    (net (code "15") (name "/DCF_L") (class "Default")
      (node (ref "R64") (pin "1") (pintype "passive"))
      (node (ref "U12") (pin "12") (pinfunction "12_12") (pintype "passive"))
    )
    (net (code "16") (name "/DCF_LG") (class "Default")
      (node (ref "R33") (pin "2") (pintype "passive"))
      (node (ref "U12") (pin "9") (pinfunction "9_9") (pintype "passive"))
    )
    (net (code "17") (name "/DCF_R") (class "Default")
      (node (ref "R53") (pin "1") (pintype "passive"))
      (node (ref "U12") (pin "11") (pinfunction "11_11") (pintype "passive"))
    )
    (net (code "18") (name "/DC_MO") (class "Default")
      (node (ref "R60") (pin "2") (pintype "passive"))
      (node (ref "U12") (pin "6") (pinfunction "6_6") (pintype "passive"))
    )
    (net (code "19") (name "/FUN_MO") (class "Default")
      (node (ref "R16") (pin "1") (pintype "passive"))
      (node (ref "U12") (pin "42") (pinfunction "42_42") (pintype "passive"))
    )
    (net (code "20") (name "/GRID1") (class "Default")
      (node (ref "LED9") (pin "12") (pinfunction "VCC-8xx_12") (pintype "passive"))
      (node (ref "U4") (pin "27") (pinfunction "GRID1_27") (pintype "passive"))
    )
    (net (code "21") (name "/GRID2") (class "Default")
      (node (ref "LED9") (pin "9") (pinfunction "VCC-x8x_9") (pintype "passive"))
      (node (ref "U4") (pin "26") (pinfunction "GRID2_26") (pintype "passive"))
    )
    (net (code "22") (name "/GRID3") (class "Default")
      (node (ref "LED9") (pin "8") (pinfunction "VCC-xx8_8") (pintype "passive"))
      (node (ref "U4") (pin "24") (pinfunction "GRID3_24") (pintype "passive"))
    )
    (net (code "23") (name "/GRID4") (class "Default")
      (node (ref "LED1") (pin "2") (pinfunction "2_2") (pintype "passive"))
      (node (ref "LED2") (pin "2") (pinfunction "2_2") (pintype "passive"))
      (node (ref "LED3") (pin "2") (pinfunction "2_2") (pintype "passive"))
      (node (ref "LED4") (pin "2") (pinfunction "2_2") (pintype "passive"))
      (node (ref "LED5") (pin "2") (pinfunction "2_2") (pintype "passive"))
      (node (ref "LED6") (pin "2") (pinfunction "2_2") (pintype "passive"))
      (node (ref "LED7") (pin "2") (pinfunction "2_2") (pintype "passive"))
      (node (ref "LED8") (pin "2") (pinfunction "2_2") (pintype "passive"))
      (node (ref "U4") (pin "23") (pinfunction "GRID4_23") (pintype "passive"))
    )
    (net (code "24") (name "/GRID5") (class "Default")
      (node (ref "LED10") (pin "2") (pinfunction "2_2") (pintype "passive"))
      (node (ref "LED11") (pin "2") (pinfunction "2_2") (pintype "passive"))
      (node (ref "LED12") (pin "2") (pinfunction "2_2") (pintype "passive"))
      (node (ref "LED13") (pin "2") (pinfunction "2_2") (pintype "passive"))
      (node (ref "LED14") (pin "2") (pinfunction "2_2") (pintype "passive"))
      (node (ref "LED15") (pin "2") (pinfunction "2_2") (pintype "passive"))
      (node (ref "LED16") (pin "2") (pinfunction "2_2") (pintype "passive"))
      (node (ref "LED17") (pin "2") (pinfunction "2_2") (pintype "passive"))
      (node (ref "U4") (pin "20") (pinfunction "GRID5_20") (pintype "passive"))
    )
    (net (code "25") (name "/GRID6") (class "Default")
      (node (ref "LED18") (pin "2") (pinfunction "2_2") (pintype "passive"))
      (node (ref "LED19") (pin "2") (pinfunction "2_2") (pintype "passive"))
      (node (ref "LED20") (pin "2") (pinfunction "2_2") (pintype "passive"))
      (node (ref "LED21") (pin "2") (pinfunction "2_2") (pintype "passive"))
      (node (ref "LED22") (pin "2") (pinfunction "2_2") (pintype "passive"))
      (node (ref "LED23") (pin "2") (pinfunction "2_2") (pintype "passive"))
      (node (ref "LED24") (pin "2") (pinfunction "2_2") (pintype "passive"))
      (node (ref "U4") (pin "19") (pinfunction "GRID6_19") (pintype "passive"))
    )
    (net (code "26") (name "/GRID7") (class "Default")
      (node (ref "U4") (pin "18") (pinfunction "GRID7_18") (pintype "passive"))
    )
    (net (code "27") (name "/IR") (class "Default")
      (node (ref "R25") (pin "1") (pinfunction "1_1") (pintype "passive"))
      (node (ref "U12") (pin "34") (pinfunction "34_34") (pintype "passive"))
    )
    (net (code "28") (name "/ISP_CK") (class "Default")
      (node (ref "J10") (pin "3") (pinfunction "3_3") (pintype "passive"))
      (node (ref "U12") (pin "44") (pinfunction "44_44") (pintype "passive"))
    )
    (net (code "29") (name "/ISP_DA") (class "Default")
      (node (ref "J10") (pin "2") (pinfunction "2_2") (pintype "passive"))
      (node (ref "U12") (pin "43") (pinfunction "43_43") (pintype "passive"))
    )
    (net (code "30") (name "/K1") (class "Default")
      (node (ref "K1") (pin "2") (pinfunction "2_2") (pintype "passive"))
      (node (ref "U12") (pin "26") (pinfunction "26_26") (pintype "passive"))
    )
    (net (code "31") (name "/K2") (class "Default")
      (node (ref "K2") (pin "2") (pinfunction "2_2") (pintype "passive"))
      (node (ref "U12") (pin "25") (pinfunction "25_25") (pintype "passive"))
    )
    (net (code "32") (name "/K3") (class "Default")
      (node (ref "K3") (pin "2") (pinfunction "2_2") (pintype "passive"))
      (node (ref "U12") (pin "24") (pinfunction "24_24") (pintype "passive"))
    )
    (net (code "33") (name "/K4") (class "Default")
      (node (ref "K4") (pin "2") (pinfunction "2_2") (pintype "passive"))
      (node (ref "U12") (pin "22") (pinfunction "22_22") (pintype "passive"))
    )
    (net (code "34") (name "/K5") (class "Default")
      (node (ref "K5") (pin "2") (pinfunction "2_2") (pintype "passive"))
      (node (ref "U12") (pin "20") (pinfunction "20_20") (pintype "passive"))
    )
    (net (code "35") (name "/K6") (class "Default")
      (node (ref "K6") (pin "2") (pinfunction "2_2") (pintype "passive"))
      (node (ref "U12") (pin "21") (pinfunction "21_21") (pintype "passive"))
    )
    (net (code "36") (name "/K7") (class "Default")
      (node (ref "K7") (pin "2") (pinfunction "2_2") (pintype "passive"))
      (node (ref "U12") (pin "23") (pinfunction "23_23") (pintype "passive"))
    )
    (net (code "37") (name "/K8") (class "Default")
      (node (ref "K8") (pin "2") (pinfunction "2_2") (pintype "passive"))
      (node (ref "U12") (pin "27") (pinfunction "27_27") (pintype "passive"))
    )
    (net (code "38") (name "/K9") (class "Default")
      (node (ref "K9") (pin "2") (pinfunction "2_2") (pintype "passive"))
      (node (ref "U12") (pin "28") (pinfunction "28_28") (pintype "passive"))
    )
    (net (code "39") (name "/K10") (class "Default")
      (node (ref "K10") (pin "2") (pinfunction "2_2") (pintype "passive"))
      (node (ref "U12") (pin "29") (pinfunction "29_29") (pintype "passive"))
    )
    (net (code "40") (name "/K11") (class "Default")
      (node (ref "K11") (pin "2") (pinfunction "2_2") (pintype "passive"))
      (node (ref "U12") (pin "30") (pinfunction "30_30") (pintype "passive"))
    )
    (net (code "41") (name "/K12") (class "Default")
      (node (ref "K12") (pin "2") (pinfunction "2_2") (pintype "passive"))
      (node (ref "U12") (pin "31") (pinfunction "31_31") (pintype "passive"))
    )
    (net (code "42") (name "/K13") (class "Default")
      (node (ref "K13") (pin "2") (pinfunction "2_2") (pintype "passive"))
      (node (ref "U12") (pin "32") (pinfunction "32_32") (pintype "passive"))
    )
    (net (code "43") (name "/K14") (class "Default")
      (node (ref "K14") (pin "2") (pinfunction "2_2") (pintype "passive"))
      (node (ref "U12") (pin "19") (pinfunction "19_19") (pintype "passive"))
    )
    (net (code "44") (name "/K15") (class "Default")
      (node (ref "K15") (pin "2") (pinfunction "2_2") (pintype "passive"))
      (node (ref "U12") (pin "18") (pinfunction "18_18") (pintype "passive"))
    )
    (net (code "45") (name "/K16") (class "Default")
      (node (ref "K16") (pin "2") (pinfunction "2_2") (pintype "passive"))
      (node (ref "U12") (pin "17") (pinfunction "17_17") (pintype "passive"))
    )
    (net (code "46") (name "/K17") (class "Default")
      (node (ref "K17") (pin "2") (pinfunction "2_2") (pintype "passive"))
      (node (ref "U12") (pin "16") (pinfunction "16_16") (pintype "passive"))
    )
    (net (code "47") (name "/K18") (class "Default")
      (node (ref "K18") (pin "2") (pinfunction "2_2") (pintype "passive"))
      (node (ref "U12") (pin "15") (pinfunction "15_15") (pintype "passive"))
    )
    (net (code "48") (name "/K19") (class "Default")
      (node (ref "K19") (pin "2") (pinfunction "2_2") (pintype "passive"))
      (node (ref "U12") (pin "14") (pinfunction "14_14") (pintype "passive"))
    )
    (net (code "49") (name "/K20") (class "Default")
      (node (ref "K20") (pin "2") (pinfunction "2_2") (pintype "passive"))
      (node (ref "U12") (pin "13") (pinfunction "13_13") (pintype "passive"))
    )
    (net (code "50") (name "/L") (class "Default")
      (node (ref "J1") (pin "1") (pinfunction "1_1") (pintype "passive"))
      (node (ref "J2") (pin "2") (pinfunction "2_2") (pintype "passive"))
      (node (ref "R13") (pin "2") (pintype "passive"))
      (node (ref "R3") (pin "2") (pintype "passive"))
      (node (ref "R4") (pin "2") (pintype "passive"))
      (node (ref "R66") (pin "1") (pintype "passive"))
      (node (ref "R67") (pin "1") (pintype "passive"))
      (node (ref "TC1") (pin "2") (pintype "passive"))
      (node (ref "TR1") (pin "2") (pintype "passive"))
      (node (ref "TR2") (pin "2") (pintype "passive"))
      (node (ref "VDR1") (pin "1") (pinfunction "1_1") (pintype "passive"))
    )
    (net (code "51") (name "/LEG") (class "Default")
      (node (ref "C16") (pin "2") (pinfunction "2_2") (pintype "passive"))
      (node (ref "D1") (pin "1") (pinfunction "A_1") (pintype "passive"))
      (node (ref "J7") (pin "2") (pinfunction "2_2") (pintype "passive"))
      (node (ref "Q3") (pin "C") (pinfunction "C_C") (pintype "passive"))
    )
    (net (code "52") (name "/Left") (class "Default")
      (node (ref "C19") (pin "2") (pinfunction "2_2") (pintype "passive"))
      (node (ref "D5") (pin "1") (pinfunction "A_1") (pintype "passive"))
      (node (ref "J7") (pin "6") (pinfunction "6_6") (pintype "passive"))
      (node (ref "Q7") (pin "C") (pinfunction "C_C") (pintype "passive"))
    )
    (net (code "53") (name "/N") (class "Default")
      (node (ref "J1") (pin "2") (pinfunction "2_2") (pintype "passive"))
      (node (ref "J2") (pin "1") (pinfunction "1_1") (pintype "passive"))
      (node (ref "J3") (pin "2") (pinfunction "2_2") (pintype "passive"))
      (node (ref "J4") (pin "2") (pinfunction "2_2") (pintype "passive"))
      (node (ref "R1") (pin "2") (pintype "passive"))
      (node (ref "TC1") (pin "1") (pintype "passive"))
      (node (ref "VDR1") (pin "2") (pinfunction "2_2") (pintype "passive"))
    )
    (net (code "54") (name "/P_KEY") (class "Default")
      (node (ref "SW1") (pin "2") (pinfunction "2_2") (pintype "passive"))
      (node (ref "U12") (pin "5") (pinfunction "5_5") (pintype "passive"))
    )
    (net (code "55") (name "/Right") (class "Default")
      (node (ref "C21") (pin "2") (pinfunction "2_2") (pintype "passive"))
      (node (ref "D6") (pin "1") (pinfunction "A_1") (pintype "passive"))
      (node (ref "J7") (pin "8") (pinfunction "8_8") (pintype "passive"))
      (node (ref "Q9") (pin "C") (pinfunction "C_C") (pintype "passive"))
    )
    (net (code "56") (name "/S1_AD") (class "Default")
      (node (ref "R65") (pin "1") (pinfunction "1_1") (pintype "passive"))
      (node (ref "U12") (pin "36") (pinfunction "36_36") (pintype "passive"))
    )
    (net (code "57") (name "/S2_AD") (class "Default")
      (node (ref "R45") (pin "1") (pinfunction "1_1") (pintype "passive"))
      (node (ref "U12") (pin "35") (pinfunction "35_35") (pintype "passive"))
    )
    (net (code "58") (name "/SEGA") (class "Default")
      (node (ref "LED1") (pin "1") (pinfunction "1_1") (pintype "passive"))
      (node (ref "LED10") (pin "1") (pinfunction "1_1") (pintype "passive"))
      (node (ref "LED18") (pin "1") (pinfunction "1_1") (pintype "passive"))
      (node (ref "LED9") (pin "11") (pinfunction "a_11") (pintype "passive"))
      (node (ref "U4") (pin "8") (pinfunction "SEG1_8") (pintype "passive"))
    )
    (net (code "59") (name "/SEGB") (class "Default")
      (node (ref "LED11") (pin "1") (pinfunction "1_1") (pintype "passive"))
      (node (ref "LED19") (pin "1") (pinfunction "1_1") (pintype "passive"))
      (node (ref "LED2") (pin "1") (pinfunction "1_1") (pintype "passive"))
      (node (ref "LED9") (pin "7") (pinfunction "b_7") (pintype "passive"))
      (node (ref "U4") (pin "9") (pinfunction "SEG2_9") (pintype "passive"))
    )
    (net (code "60") (name "/SEGC") (class "Default")
      (node (ref "LED12") (pin "1") (pinfunction "1_1") (pintype "passive"))
      (node (ref "LED20") (pin "1") (pinfunction "1_1") (pintype "passive"))
      (node (ref "LED3") (pin "1") (pinfunction "1_1") (pintype "passive"))
      (node (ref "LED9") (pin "4") (pinfunction "c_4") (pintype "passive"))
      (node (ref "U4") (pin "10") (pinfunction "SEG3_10") (pintype "passive"))
    )
    (net (code "61") (name "/SEGD") (class "Default")
      (node (ref "LED13") (pin "1") (pinfunction "1_1") (pintype "passive"))
      (node (ref "LED21") (pin "1") (pinfunction "1_1") (pintype "passive"))
      (node (ref "LED4") (pin "1") (pinfunction "1_1") (pintype "passive"))
      (node (ref "LED9") (pin "2") (pinfunction "d_2") (pintype "passive"))
      (node (ref "U4") (pin "11") (pinfunction "SEG4_11") (pintype "passive"))
    )
    (net (code "62") (name "/SEGE") (class "Default")
      (node (ref "LED14") (pin "1") (pinfunction "1_1") (pintype "passive"))
      (node (ref "LED22") (pin "1") (pinfunction "1_1") (pintype "passive"))
      (node (ref "LED5") (pin "1") (pinfunction "1_1") (pintype "passive"))
      (node (ref "LED9") (pin "1") (pinfunction "e_1") (pintype "passive"))
      (node (ref "U4") (pin "12") (pinfunction "SEG5_12") (pintype "passive"))
    )
    (net (code "63") (name "/SEGF") (class "Default")
      (node (ref "LED15") (pin "1") (pinfunction "1_1") (pintype "passive"))
      (node (ref "LED23") (pin "1") (pinfunction "1_1") (pintype "passive"))
      (node (ref "LED6") (pin "1") (pinfunction "1_1") (pintype "passive"))
      (node (ref "LED9") (pin "10") (pinfunction "f_10") (pintype "passive"))
      (node (ref "U4") (pin "13") (pinfunction "SEG6_13") (pintype "passive"))
    )
    (net (code "64") (name "/SEGG") (class "Default")
      (node (ref "LED16") (pin "1") (pinfunction "1_1") (pintype "passive"))
      (node (ref "LED7") (pin "1") (pinfunction "1_1") (pintype "passive"))
      (node (ref "LED9") (pin "5") (pinfunction "g_5") (pintype "passive"))
      (node (ref "U4") (pin "14") (pinfunction "SEG7_14") (pintype "passive"))
    )
    (net (code "65") (name "/SEGH") (class "Default")
      (node (ref "LED17") (pin "1") (pinfunction "1_1") (pintype "passive"))
      (node (ref "LED24") (pin "1") (pinfunction "1_1") (pintype "passive"))
      (node (ref "LED8") (pin "1") (pinfunction "1_1") (pintype "passive"))
      (node (ref "LED9") (pin "3") (pinfunction "uc_3") (pintype "passive"))
      (node (ref "U4") (pin "15") (pinfunction "SEG8_15") (pintype "passive"))
    )
    (net (code "66") (name "/STB") (class "Default")
      (node (ref "R11") (pin "1") (pinfunction "1_1") (pintype "passive"))
      (node (ref "U12") (pin "1") (pinfunction "1_1") (pintype "passive"))
    )
    (net (code "67") (name "/Zero") (class "Default")
      (node (ref "R2") (pin "2") (pintype "passive"))
      (node (ref "U1") (pin "4") (pinfunction "COL_4") (pintype "passive"))
      (node (ref "U12") (pin "33") (pinfunction "33_33") (pintype "passive"))
    )
    (net (code "68") (name "5V") (class "Default")
      (node (ref "C1") (pin "2") (pinfunction "2_2") (pintype "passive"))
      (node (ref "C10") (pin "1") (pinfunction "1_1") (pintype "passive"))
      (node (ref "C2") (pin "2") (pinfunction "2_2") (pintype "passive"))
      (node (ref "C23") (pin "1") (pinfunction "1_1") (pintype "passive"))
      (node (ref "C8") (pin "1") (pinfunction "1_1") (pintype "passive"))
      (node (ref "C9") (pin "1") (pinfunction "1_1") (pintype "passive"))
      (node (ref "EC1") (pin "1") (pinfunction "1_1") (pintype "passive"))
      (node (ref "J10") (pin "4") (pinfunction "4_4") (pintype "passive"))
      (node (ref "L1") (pin "2") (pinfunction "2_2") (pintype "passive"))
      (node (ref "R14") (pin "1") (pintype "passive"))
      (node (ref "R2") (pin "1") (pintype "passive"))
      (node (ref "R20") (pin "1") (pinfunction "1_1") (pintype "passive"))
      (node (ref "R23") (pin "1") (pinfunction "1_1") (pintype "passive"))
      (node (ref "R28") (pin "1") (pinfunction "1_1") (pintype "passive"))
      (node (ref "R30") (pin "1") (pinfunction "1_1") (pintype "passive"))
      (node (ref "R48") (pin "1") (pinfunction "1_1") (pintype "passive"))
      (node (ref "R51") (pin "1") (pinfunction "1_1") (pintype "passive"))
      (node (ref "R6") (pin "1") (pintype "passive"))
      (node (ref "U10") (pin "4") (pinfunction "4_4") (pintype "passive"))
      (node (ref "U12") (pin "37") (pinfunction "37_37") (pintype "passive"))
      (node (ref "U13") (pin "4") (pinfunction "4_4") (pintype "passive"))
      (node (ref "U4") (pin "21") (pinfunction "VDD_21") (pintype "passive"))
      (node (ref "U4") (pin "7") (pinfunction "VDD_7") (pintype "passive"))
      (node (ref "U7") (pin "6") (pinfunction "6_6") (pintype "passive"))
    )
    (net (code "69") (name "GND") (class "Default")
      (node (ref "BUZZ1") (pin "1") (pinfunction "1_1") (pintype "passive"))
      (node (ref "C1") (pin "1") (pinfunction "1_1") (pintype "passive"))
      (node (ref "C10") (pin "2") (pinfunction "2_2") (pintype "passive"))
      (node (ref "C12") (pin "1") (pinfunction "1_1") (pintype "passive"))
      (node (ref "C13") (pin "1") (pinfunction "1_1") (pintype "passive"))
      (node (ref "C14") (pin "2") (pinfunction "2_2") (pintype "passive"))
      (node (ref "C15") (pin "1") (pinfunction "1_1") (pintype "passive"))
      (node (ref "C17") (pin "1") (pinfunction "1_1") (pintype "passive"))
      (node (ref "C2") (pin "1") (pinfunction "1_1") (pintype "passive"))
      (node (ref "C23") (pin "2") (pinfunction "2_2") (pintype "passive"))
      (node (ref "C25") (pin "1") (pinfunction "1_1") (pintype "passive"))
      (node (ref "C3") (pin "2") (pinfunction "2_2") (pintype "passive"))
      (node (ref "C4") (pin "2") (pinfunction "2_2") (pintype "passive"))
      (node (ref "C6") (pin "2") (pinfunction "2_2") (pintype "passive"))
      (node (ref "C7") (pin "1") (pinfunction "1_1") (pintype "passive"))
      (node (ref "C8") (pin "2") (pinfunction "2_2") (pintype "passive"))
      (node (ref "C9") (pin "2") (pinfunction "2_2") (pintype "passive"))
      (node (ref "EC1") (pin "2") (pinfunction "2_2") (pintype "passive"))
      (node (ref "J10") (pin "1") (pinfunction "1_1") (pintype "passive"))
      (node (ref "J5") (pin "2") (pinfunction "2_2") (pintype "passive"))
      (node (ref "L2") (pin "1") (pinfunction "1_1") (pintype "passive"))
      (node (ref "L3") (pin "1") (pinfunction "1_1") (pintype "passive"))
      (node (ref "Q1") (pin "E") (pinfunction "E_E") (pintype "passive"))
      (node (ref "Q2") (pin "E") (pinfunction "E_E") (pintype "passive"))
      (node (ref "Q3") (pin "E") (pinfunction "E_E") (pintype "passive"))
      (node (ref "Q4") (pin "E") (pinfunction "E_E") (pintype "passive"))
      (node (ref "Q5") (pin "E") (pinfunction "E_E") (pintype "passive"))
      (node (ref "Q6") (pin "E") (pinfunction "E_E") (pintype "passive"))
      (node (ref "Q7") (pin "E") (pinfunction "E_E") (pintype "passive"))
      (node (ref "Q8") (pin "E") (pinfunction "E_E") (pintype "passive"))
      (node (ref "Q9") (pin "E") (pinfunction "E_E") (pintype "passive"))
      (node (ref "R15") (pin "2") (pintype "passive"))
      (node (ref "R17") (pin "2") (pinfunction "2_2") (pintype "passive"))
      (node (ref "R21") (pin "2") (pinfunction "2_2") (pintype "passive"))
      (node (ref "R27") (pin "2") (pintype "passive"))
      (node (ref "R29") (pin "2") (pinfunction "2_2") (pintype "passive"))
      (node (ref "R32") (pin "2") (pintype "passive"))
      (node (ref "R36") (pin "2") (pinfunction "2_2") (pintype "passive"))
      (node (ref "R38") (pin "2") (pinfunction "2_2") (pintype "passive"))
      (node (ref "R40") (pin "2") (pintype "passive"))
      (node (ref "R42") (pin "2") (pintype "passive"))
      (node (ref "R49") (pin "2") (pinfunction "2_2") (pintype "passive"))
      (node (ref "R50") (pin "2") (pintype "passive"))
      (node (ref "R55") (pin "2") (pintype "passive"))
      (node (ref "R56") (pin "2") (pinfunction "2_2") (pintype "passive"))
      (node (ref "R58") (pin "2") (pinfunction "2_2") (pintype "passive"))
      (node (ref "R61") (pin "2") (pintype "passive"))
      (node (ref "R7") (pin "2") (pintype "passive"))
      (node (ref "SW1") (pin "1") (pinfunction "1_1") (pintype "passive"))
      (node (ref "U1") (pin "3") (pinfunction "EM_3") (pintype "passive"))
      (node (ref "U10") (pin "11") (pinfunction "11_11") (pintype "passive"))
      (node (ref "U12") (pin "40") (pinfunction "40_40") (pintype "passive"))
      (node (ref "U13") (pin "11") (pinfunction "11_11") (pintype "passive"))
      (node (ref "U4") (pin "22") (pinfunction "GND_22") (pintype "passive"))
      (node (ref "U4") (pin "25") (pinfunction "GND_25") (pintype "passive"))
      (node (ref "U4") (pin "28") (pinfunction "GND_28") (pintype "passive"))
      (node (ref "U6") (pin "2") (pinfunction "2_2") (pintype "passive"))
      (node (ref "U7") (pin "8") (pinfunction "8_8") (pintype "passive"))
      (node (ref "U9") (pin "1") (pinfunction "1_1") (pintype "passive"))
      (node (ref "U9") (pin "6") (pinfunction "6_6") (pintype "passive"))
      (node (ref "Y1") (pin "2") (pinfunction "OSC2_2") (pintype "passive"))
    )
    (net (code "70") (name "Net-(BUZZ1-Pad2)") (class "Default")
      (node (ref "BUZZ1") (pin "2") (pinfunction "2_2") (pintype "passive"))
      (node (ref "R18") (pin "1") (pinfunction "1_1") (pintype "passive"))
      (node (ref "R21") (pin "1") (pinfunction "1_1") (pintype "passive"))
    )
    (net (code "71") (name "Net-(C5-Pad1)") (class "Default")
      (node (ref "C5") (pin "1") (pinfunction "1_1") (pintype "passive"))
      (node (ref "U6") (pin "1") (pinfunction "1_1") (pintype "passive"))
    )
    (net (code "72") (name "Net-(C5-Pad2)") (class "Default")
      (node (ref "C5") (pin "2") (pinfunction "2_2") (pintype "passive"))
      (node (ref "L1") (pin "1") (pinfunction "1_1") (pintype "passive"))
      (node (ref "R24") (pin "2") (pinfunction "2_2") (pintype "passive"))
      (node (ref "U6") (pin "6") (pinfunction "6_6") (pintype "passive"))
    )
    (net (code "73") (name "Net-(C6-Pad1)") (class "Default")
      (node (ref "C6") (pin "1") (pinfunction "1_1") (pintype "passive"))
      (node (ref "R23") (pin "2") (pinfunction "2_2") (pintype "passive"))
      (node (ref "U9") (pin "3") (pinfunction "3_3") (pintype "passive"))
    )
    (net (code "74") (name "Net-(C7-Pad2)") (class "Default")
      (node (ref "C7") (pin "2") (pinfunction "2_2") (pintype "passive"))
      (node (ref "R24") (pin "1") (pinfunction "1_1") (pintype "passive"))
    )
    (net (code "75") (name "Net-(C11-Pad2)") (class "Default")
      (node (ref "C11") (pin "2") (pinfunction "2_2") (pintype "passive"))
      (node (ref "L2") (pin "2") (pinfunction "2_2") (pintype "passive"))
      (node (ref "U9") (pin "2") (pinfunction "2_2") (pintype "passive"))
    )
    (net (code "76") (name "Net-(C12-Pad2)") (class "Default")
      (node (ref "C12") (pin "2") (pinfunction "2_2") (pintype "passive"))
      (node (ref "U10") (pin "1") (pinfunction "1_1") (pintype "passive"))
      (node (ref "U8") (pin "2") (pinfunction "2_2") (pintype "passive"))
    )
    (net (code "77") (name "Net-(C14-Pad1)") (class "Default")
      (node (ref "C14") (pin "1") (pinfunction "1_1") (pintype "passive"))
      (node (ref "U9") (pin "4") (pinfunction "4_4") (pintype "passive"))
    )
    (net (code "78") (name "Net-(C15-Pad2)") (class "Default")
      (node (ref "C15") (pin "2") (pinfunction "2_2") (pintype "passive"))
      (node (ref "R30") (pin "2") (pinfunction "2_2") (pintype "passive"))
      (node (ref "R34") (pin "2") (pinfunction "2_2") (pintype "passive"))
      (node (ref "R38") (pin "1") (pinfunction "1_1") (pintype "passive"))
    )
    (net (code "79") (name "Net-(C17-Pad2)") (class "Default")
      (node (ref "C17") (pin "2") (pinfunction "2_2") (pintype "passive"))
      (node (ref "U11") (pin "2") (pinfunction "2_2") (pintype "passive"))
      (node (ref "U13") (pin "1") (pinfunction "1_1") (pintype "passive"))
    )
    (net (code "80") (name "Net-(C25-Pad2)") (class "Default")
      (node (ref "C25") (pin "2") (pinfunction "2_2") (pintype "passive"))
      (node (ref "R51") (pin "2") (pinfunction "2_2") (pintype "passive"))
      (node (ref "R54") (pin "2") (pinfunction "2_2") (pintype "passive"))
      (node (ref "R58") (pin "1") (pinfunction "1_1") (pintype "passive"))
    )
    (net (code "81") (name "Net-(C26-Pad1)") (class "Default")
      (node (ref "C26") (pin "1") (pinfunction "1_1") (pintype "passive"))
      (node (ref "R66") (pin "2") (pintype "passive"))
    )
    (net (code "82") (name "Net-(C26-Pad2)") (class "Default")
      (node (ref "C26") (pin "2") (pinfunction "2_2") (pintype "passive"))
      (node (ref "J3") (pin "1") (pinfunction "1_1") (pintype "passive"))
      (node (ref "TR1") (pin "1") (pintype "passive"))
    )
    (net (code "83") (name "Net-(C27-Pad1)") (class "Default")
      (node (ref "C27") (pin "1") (pinfunction "1_1") (pintype "passive"))
      (node (ref "R67") (pin "2") (pintype "passive"))
    )
    (net (code "84") (name "Net-(C27-Pad2)") (class "Default")
      (node (ref "C27") (pin "2") (pinfunction "2_2") (pintype "passive"))
      (node (ref "J4") (pin "1") (pinfunction "1_1") (pintype "passive"))
      (node (ref "TR2") (pin "1") (pintype "passive"))
    )
    (net (code "85") (name "Net-(D7-A)") (class "Default")
      (node (ref "C20") (pin "2") (pinfunction "2_2") (pintype "passive"))
      (node (ref "D7") (pin "1") (pinfunction "A_1") (pintype "passive"))
      (node (ref "J9") (pin "1") (pinfunction "1_1") (pintype "passive"))
      (node (ref "Q8") (pin "C") (pinfunction "C_C") (pintype "passive"))
    )
    (net (code "86") (name "Net-(J6-Pad1)") (class "Default")
      (node (ref "J6") (pin "1") (pinfunction "1_1") (pintype "passive"))
      (node (ref "U7") (pin "5") (pinfunction "5_5") (pintype "passive"))
    )
    (net (code "87") (name "Net-(J6-Pad2)") (class "Default")
      (node (ref "J6") (pin "2") (pinfunction "2_2") (pintype "passive"))
      (node (ref "U7") (pin "7") (pinfunction "7_7") (pintype "passive"))
    )
    (net (code "88") (name "Net-(Q1-PadB)") (class "Default")
      (node (ref "Q1") (pin "B") (pinfunction "B_B") (pintype "passive"))
      (node (ref "R7") (pin "1") (pintype "passive"))
      (node (ref "R9") (pin "2") (pintype "passive"))
    )
    (net (code "89") (name "Net-(Q2-PadB)") (class "Default")
      (node (ref "Q2") (pin "B") (pinfunction "B_B") (pintype "passive"))
      (node (ref "R15") (pin "1") (pintype "passive"))
      (node (ref "R16") (pin "2") (pintype "passive"))
    )
    (net (code "90") (name "Net-(Q3-PadB)") (class "Default")
      (node (ref "Q3") (pin "B") (pinfunction "B_B") (pintype "passive"))
      (node (ref "R27") (pin "1") (pintype "passive"))
      (node (ref "R33") (pin "1") (pintype "passive"))
    )
    (net (code "91") (name "Net-(Q4-PadB)") (class "Default")
      (node (ref "Q4") (pin "B") (pinfunction "B_B") (pintype "passive"))
      (node (ref "R32") (pin "1") (pintype "passive"))
      (node (ref "R35") (pin "1") (pintype "passive"))
    )
    (net (code "92") (name "Net-(Q5-PadB)") (class "Default")
      (node (ref "Q5") (pin "B") (pinfunction "B_B") (pintype "passive"))
      (node (ref "R40") (pin "1") (pintype "passive"))
      (node (ref "R44") (pin "2") (pintype "passive"))
    )
    (net (code "93") (name "Net-(Q6-PadB)") (class "Default")
      (node (ref "Q6") (pin "B") (pinfunction "B_B") (pintype "passive"))
      (node (ref "R42") (pin "1") (pintype "passive"))
      (node (ref "R46") (pin "1") (pintype "passive"))
    )
    (net (code "94") (name "Net-(Q7-PadB)") (class "Default")
      (node (ref "Q7") (pin "B") (pinfunction "B_B") (pintype "passive"))
      (node (ref "R50") (pin "1") (pintype "passive"))
      (node (ref "R53") (pin "2") (pintype "passive"))
    )
    (net (code "95") (name "Net-(Q8-PadB)") (class "Default")
      (node (ref "Q8") (pin "B") (pinfunction "B_B") (pintype "passive"))
      (node (ref "R55") (pin "1") (pintype "passive"))
      (node (ref "R60") (pin "1") (pintype "passive"))
    )
    (net (code "96") (name "Net-(Q9-PadB)") (class "Default")
      (node (ref "Q9") (pin "B") (pinfunction "B_B") (pintype "passive"))
      (node (ref "R61") (pin "1") (pintype "passive"))
      (node (ref "R64") (pin "2") (pintype "passive"))
    )
    (net (code "97") (name "Net-(R1-Pad1)") (class "Default")
      (node (ref "R1") (pin "1") (pintype "passive"))
      (node (ref "U2") (pin "AC2") (pinfunction "～_AC2") (pintype "passive"))
    )
    (net (code "98") (name "Net-(R3-Pad1)") (class "Default")
      (node (ref "R3") (pin "1") (pintype "passive"))
      (node (ref "U2") (pin "AC1") (pinfunction "～_AC1") (pintype "passive"))
    )
    (net (code "99") (name "Net-(R4-Pad1)") (class "Default")
      (node (ref "R4") (pin "1") (pintype "passive"))
      (node (ref "R5") (pin "1") (pintype "passive"))
    )
    (net (code "100") (name "Net-(R12-Pad1)") (class "Default")
      (node (ref "R12") (pin "1") (pintype "passive"))
      (node (ref "R13") (pin "1") (pintype "passive"))
    )
    (net (code "101") (name "Net-(R17-Pad1)") (class "Default")
      (node (ref "R17") (pin "1") (pinfunction "1_1") (pintype "passive"))
      (node (ref "R20") (pin "2") (pinfunction "2_2") (pintype "passive"))
      (node (ref "U6") (pin "3") (pinfunction "3_3") (pintype "passive"))
    )
    (net (code "102") (name "Net-(R19-Pad2)") (class "Default")
      (node (ref "R19") (pin "2") (pinfunction "2_2") (pintype "passive"))
      (node (ref "U6") (pin "4") (pinfunction "4_4") (pintype "passive"))
    )
    (net (code "103") (name "Net-(R22-Pad2)") (class "Default")
      (node (ref "R22") (pin "2") (pinfunction "2_2") (pintype "passive"))
      (node (ref "U7") (pin "2") (pinfunction "2_2") (pintype "passive"))
    )
    (net (code "104") (name "Net-(R25-Pad2)") (class "Default")
      (node (ref "R25") (pin "2") (pinfunction "2_2") (pintype "passive"))
      (node (ref "U9") (pin "5") (pinfunction "5_5") (pintype "passive"))
    )
    (net (code "105") (name "Net-(R26-Pad1)") (class "Default")
      (node (ref "R26") (pin "1") (pinfunction "1_1") (pintype "passive"))
      (node (ref "R31") (pin "1") (pinfunction "1_1") (pintype "passive"))
      (node (ref "U10") (pin "14") (pinfunction "14_14") (pintype "passive"))
    )
    (net (code "106") (name "Net-(R26-Pad2)") (class "Default")
      (node (ref "R26") (pin "2") (pinfunction "2_2") (pintype "passive"))
      (node (ref "R34") (pin "1") (pinfunction "1_1") (pintype "passive"))
      (node (ref "U10") (pin "5") (pinfunction "5_5") (pintype "passive"))
    )
    (net (code "107") (name "Net-(R28-Pad2)") (class "Default")
      (node (ref "R28") (pin "2") (pinfunction "2_2") (pintype "passive"))
      (node (ref "R36") (pin "1") (pinfunction "1_1") (pintype "passive"))
      (node (ref "U10") (pin "3") (pinfunction "3_3") (pintype "passive"))
    )
    (net (code "108") (name "Net-(R29-Pad1)") (class "Default")
      (node (ref "R29") (pin "1") (pinfunction "1_1") (pintype "passive"))
      (node (ref "U10") (pin "2") (pinfunction "2_2") (pintype "passive"))
      (node (ref "U8") (pin "5") (pinfunction "5_5") (pintype "passive"))
    )
    (net (code "109") (name "Net-(R31-Pad2)") (class "Default")
      (node (ref "R31") (pin "2") (pinfunction "2_2") (pintype "passive"))
      (node (ref "R37") (pin "1") (pinfunction "1_1") (pintype "passive"))
      (node (ref "U10") (pin "13") (pinfunction "13_13") (pintype "passive"))
    )
    (net (code "110") (name "Net-(R37-Pad2)") (class "Default")
      (node (ref "R37") (pin "2") (pinfunction "2_2") (pintype "passive"))
      (node (ref "R41") (pin "2") (pinfunction "2_2") (pintype "passive"))
      (node (ref "U10") (pin "9") (pinfunction "9_9") (pintype "passive"))
    )
    (net (code "111") (name "Net-(R39-Pad1)") (class "Default")
      (node (ref "R39") (pin "1") (pinfunction "1_1") (pintype "passive"))
      (node (ref "R43") (pin "2") (pinfunction "2_2") (pintype "passive"))
      (node (ref "U10") (pin "6") (pinfunction "6_6") (pintype "passive"))
    )
    (net (code "112") (name "Net-(R39-Pad2)") (class "Default")
      (node (ref "R39") (pin "2") (pinfunction "2_2") (pintype "passive"))
      (node (ref "R45") (pin "2") (pinfunction "2_2") (pintype "passive"))
      (node (ref "U10") (pin "7") (pinfunction "7_7") (pintype "passive"))
    )
    (net (code "113") (name "Net-(R41-Pad1)") (class "Default")
      (node (ref "R41") (pin "1") (pinfunction "1_1") (pintype "passive"))
      (node (ref "R43") (pin "1") (pinfunction "1_1") (pintype "passive"))
      (node (ref "U10") (pin "8") (pinfunction "8_8") (pintype "passive"))
    )
    (net (code "114") (name "Net-(R47-Pad1)") (class "Default")
      (node (ref "R47") (pin "1") (pinfunction "1_1") (pintype "passive"))
      (node (ref "R52") (pin "1") (pinfunction "1_1") (pintype "passive"))
      (node (ref "U13") (pin "14") (pinfunction "14_14") (pintype "passive"))
    )
    (net (code "115") (name "Net-(R47-Pad2)") (class "Default")
      (node (ref "R47") (pin "2") (pinfunction "2_2") (pintype "passive"))
      (node (ref "R54") (pin "1") (pinfunction "1_1") (pintype "passive"))
      (node (ref "U13") (pin "5") (pinfunction "5_5") (pintype "passive"))
    )
    (net (code "116") (name "Net-(R48-Pad2)") (class "Default")
      (node (ref "R48") (pin "2") (pinfunction "2_2") (pintype "passive"))
      (node (ref "R56") (pin "1") (pinfunction "1_1") (pintype "passive"))
      (node (ref "U13") (pin "3") (pinfunction "3_3") (pintype "passive"))
    )
    (net (code "117") (name "Net-(R49-Pad1)") (class "Default")
      (node (ref "R49") (pin "1") (pinfunction "1_1") (pintype "passive"))
      (node (ref "U11") (pin "5") (pinfunction "5_5") (pintype "passive"))
      (node (ref "U13") (pin "2") (pinfunction "2_2") (pintype "passive"))
    )
    (net (code "118") (name "Net-(R52-Pad2)") (class "Default")
      (node (ref "R52") (pin "2") (pinfunction "2_2") (pintype "passive"))
      (node (ref "R57") (pin "1") (pinfunction "1_1") (pintype "passive"))
      (node (ref "U13") (pin "13") (pinfunction "13_13") (pintype "passive"))
    )
    (net (code "119") (name "Net-(R57-Pad2)") (class "Default")
      (node (ref "R57") (pin "2") (pinfunction "2_2") (pintype "passive"))
      (node (ref "R62") (pin "2") (pinfunction "2_2") (pintype "passive"))
      (node (ref "U13") (pin "9") (pinfunction "9_9") (pintype "passive"))
    )
    (net (code "120") (name "Net-(R59-Pad1)") (class "Default")
      (node (ref "R59") (pin "1") (pinfunction "1_1") (pintype "passive"))
      (node (ref "R63") (pin "2") (pinfunction "2_2") (pintype "passive"))
      (node (ref "U13") (pin "6") (pinfunction "6_6") (pintype "passive"))
    )
    (net (code "121") (name "Net-(R59-Pad2)") (class "Default")
      (node (ref "R59") (pin "2") (pinfunction "2_2") (pintype "passive"))
      (node (ref "R65") (pin "2") (pinfunction "2_2") (pintype "passive"))
      (node (ref "U13") (pin "7") (pinfunction "7_7") (pintype "passive"))
    )
    (net (code "122") (name "Net-(R62-Pad1)") (class "Default")
      (node (ref "R62") (pin "1") (pinfunction "1_1") (pintype "passive"))
      (node (ref "R63") (pin "1") (pinfunction "1_1") (pintype "passive"))
      (node (ref "U13") (pin "8") (pinfunction "8_8") (pintype "passive"))
    )
    (net (code "123") (name "Net-(R68-Pad2)") (class "Default")
      (node (ref "R68") (pin "2") (pinfunction "2_2") (pintype "passive"))
      (node (ref "U7") (pin "1") (pinfunction "1_1") (pintype "passive"))
    )
    (net (code "124") (name "Net-(U1-AN)") (class "Default")
      (node (ref "U1") (pin "1") (pinfunction "AN_1") (pintype "passive"))
      (node (ref "U2") (pin "V+") (pinfunction "+_V+") (pintype "passive"))
    )
    (net (code "125") (name "Net-(U1-CAT)") (class "Default")
      (node (ref "U1") (pin "2") (pinfunction "CAT_2") (pintype "passive"))
      (node (ref "U2") (pin "V-") (pinfunction "-_V-") (pintype "passive"))
    )
    (net (code "126") (name "Net-(U3-A)") (class "Default")
      (node (ref "R6") (pin "2") (pintype "passive"))
      (node (ref "U3") (pin "1") (pinfunction "A_1") (pintype "passive"))
    )
    (net (code "127") (name "Net-(U3-C)") (class "Default")
      (node (ref "Q1") (pin "C") (pinfunction "C_C") (pintype "passive"))
      (node (ref "U3") (pin "2") (pinfunction "C_2") (pintype "passive"))
    )
    (net (code "128") (name "Net-(U3-MT1)") (class "Default")
      (node (ref "R5") (pin "2") (pintype "passive"))
      (node (ref "U3") (pin "6") (pinfunction "MT1_6") (pintype "passive"))
    )
    (net (code "129") (name "Net-(U3-MT2)") (class "Default")
      (node (ref "TR1") (pin "3") (pintype "passive"))
      (node (ref "U3") (pin "4") (pinfunction "MT2_4") (pintype "passive"))
    )
    (net (code "130") (name "Net-(U4-CLK)") (class "Default")
      (node (ref "R10") (pin "2") (pinfunction "2_2") (pintype "passive"))
      (node (ref "U4") (pin "3") (pinfunction "CLK_3") (pintype "passive"))
    )
    (net (code "131") (name "Net-(U4-DIO)") (class "Default")
      (node (ref "R8") (pin "2") (pinfunction "2_2") (pintype "passive"))
      (node (ref "U4") (pin "2") (pinfunction "DIO_2") (pintype "passive"))
    )
    (net (code "132") (name "Net-(U4-STB)") (class "Default")
      (node (ref "R11") (pin "2") (pinfunction "2_2") (pintype "passive"))
      (node (ref "U4") (pin "4") (pinfunction "STB_4") (pintype "passive"))
    )
    (net (code "133") (name "Net-(U5-A)") (class "Default")
      (node (ref "R14") (pin "2") (pintype "passive"))
      (node (ref "U5") (pin "1") (pinfunction "A_1") (pintype "passive"))
    )
    (net (code "134") (name "Net-(U5-C)") (class "Default")
      (node (ref "Q2") (pin "C") (pinfunction "C_C") (pintype "passive"))
      (node (ref "U5") (pin "2") (pinfunction "C_2") (pintype "passive"))
    )
    (net (code "135") (name "Net-(U5-MT1)") (class "Default")
      (node (ref "R12") (pin "2") (pintype "passive"))
      (node (ref "U5") (pin "6") (pinfunction "MT1_6") (pintype "passive"))
    )
    (net (code "136") (name "Net-(U5-MT2)") (class "Default")
      (node (ref "TR2") (pin "3") (pintype "passive"))
      (node (ref "U5") (pin "4") (pinfunction "MT2_4") (pintype "passive"))
    )
    (net (code "137") (name "Net-(U10-Pad10)") (class "Default")
      (node (ref "U10") (pin "10") (pinfunction "10_10") (pintype "passive"))
      (node (ref "U8") (pin "1") (pinfunction "1_1") (pintype "passive"))
      (node (ref "U8") (pin "6") (pinfunction "6_6") (pintype "passive"))
    )
    (net (code "138") (name "Net-(U10-Pad12)") (class "Default")
      (node (ref "U10") (pin "12") (pinfunction "12_12") (pintype "passive"))
      (node (ref "U8") (pin "3") (pinfunction "3_3") (pintype "passive"))
    )
    (net (code "139") (name "Net-(U11-Pad1)") (class "Default")
      (node (ref "U11") (pin "1") (pinfunction "1_1") (pintype "passive"))
      (node (ref "U11") (pin "6") (pinfunction "6_6") (pintype "passive"))
      (node (ref "U13") (pin "10") (pinfunction "10_10") (pintype "passive"))
    )
    (net (code "140") (name "Net-(U11-Pad3)") (class "Default")
      (node (ref "U11") (pin "3") (pinfunction "3_3") (pintype "passive"))
      (node (ref "U13") (pin "12") (pinfunction "12_12") (pintype "passive"))
    )
    (net (code "141") (name "Net-(Y1-OSC1)") (class "Default")
      (node (ref "U9") (pin "8") (pinfunction "8_8") (pintype "passive"))
      (node (ref "Y1") (pin "1") (pinfunction "OSC1_1") (pintype "passive"))
    )
    (net (code "142") (name "unconnected-(LED9-N-Pad6)") (class "Default")
      (node (ref "LED9") (pin "6") (pinfunction "N_6") (pintype "passive"))
    )
    (net (code "143") (name "unconnected-(U3-NC-Pad3)") (class "Default")
      (node (ref "U3") (pin "3") (pinfunction "NC_3") (pintype "passive+no_connect"))
    )
    (net (code "144") (name "unconnected-(U3-SBU-Pad5)") (class "Default")
      (node (ref "U3") (pin "5") (pinfunction "SBU_5") (pintype "passive+no_connect"))
    )
    (net (code "145") (name "unconnected-(U4-K1-Pad5)") (class "Default")
      (node (ref "U4") (pin "5") (pinfunction "K1_5") (pintype "passive"))
    )
    (net (code "146") (name "unconnected-(U4-K2-Pad6)") (class "Default")
      (node (ref "U4") (pin "6") (pinfunction "K2_6") (pintype "passive"))
    )
    (net (code "147") (name "unconnected-(U4-NC-Pad1)") (class "Default")
      (node (ref "U4") (pin "1") (pinfunction "NC_1") (pintype "passive"))
    )
    (net (code "148") (name "unconnected-(U4-SEG9-Pad16)") (class "Default")
      (node (ref "U4") (pin "16") (pinfunction "SEG9_16") (pintype "passive"))
    )
    (net (code "149") (name "unconnected-(U4-SEG10-Pad17)") (class "Default")
      (node (ref "U4") (pin "17") (pinfunction "SEG10_17") (pintype "passive"))
    )
    (net (code "150") (name "unconnected-(U5-NC-Pad3)") (class "Default")
      (node (ref "U5") (pin "3") (pinfunction "NC_3") (pintype "passive+no_connect"))
    )
    (net (code "151") (name "unconnected-(U5-SBU-Pad5)") (class "Default")
      (node (ref "U5") (pin "5") (pinfunction "SBU_5") (pintype "passive+no_connect"))
    )
    (net (code "152") (name "unconnected-(U7-Pad3)") (class "Default")
      (node (ref "U7") (pin "3") (pinfunction "3_3") (pintype "passive"))
    )
    (net (code "153") (name "unconnected-(U7-Pad4)") (class "Default")
      (node (ref "U7") (pin "4") (pinfunction "4_4") (pintype "passive"))
    )
    (net (code "154") (name "unconnected-(U8-Pad4)") (class "Default")
      (node (ref "U8") (pin "4") (pinfunction "4_4") (pintype "passive+no_connect"))
    )
    (net (code "155") (name "unconnected-(U9-Pad7)") (class "Default")
      (node (ref "U9") (pin "7") (pinfunction "7_7") (pintype "passive+no_connect"))
    )
    (net (code "156") (name "unconnected-(U11-Pad4)") (class "Default")
      (node (ref "U11") (pin "4") (pinfunction "4_4") (pintype "passive+no_connect"))
    )
  )
)
